# Breeze2_Main_V1.net
KiCad netlist of a schematic drawn in Altium Designer
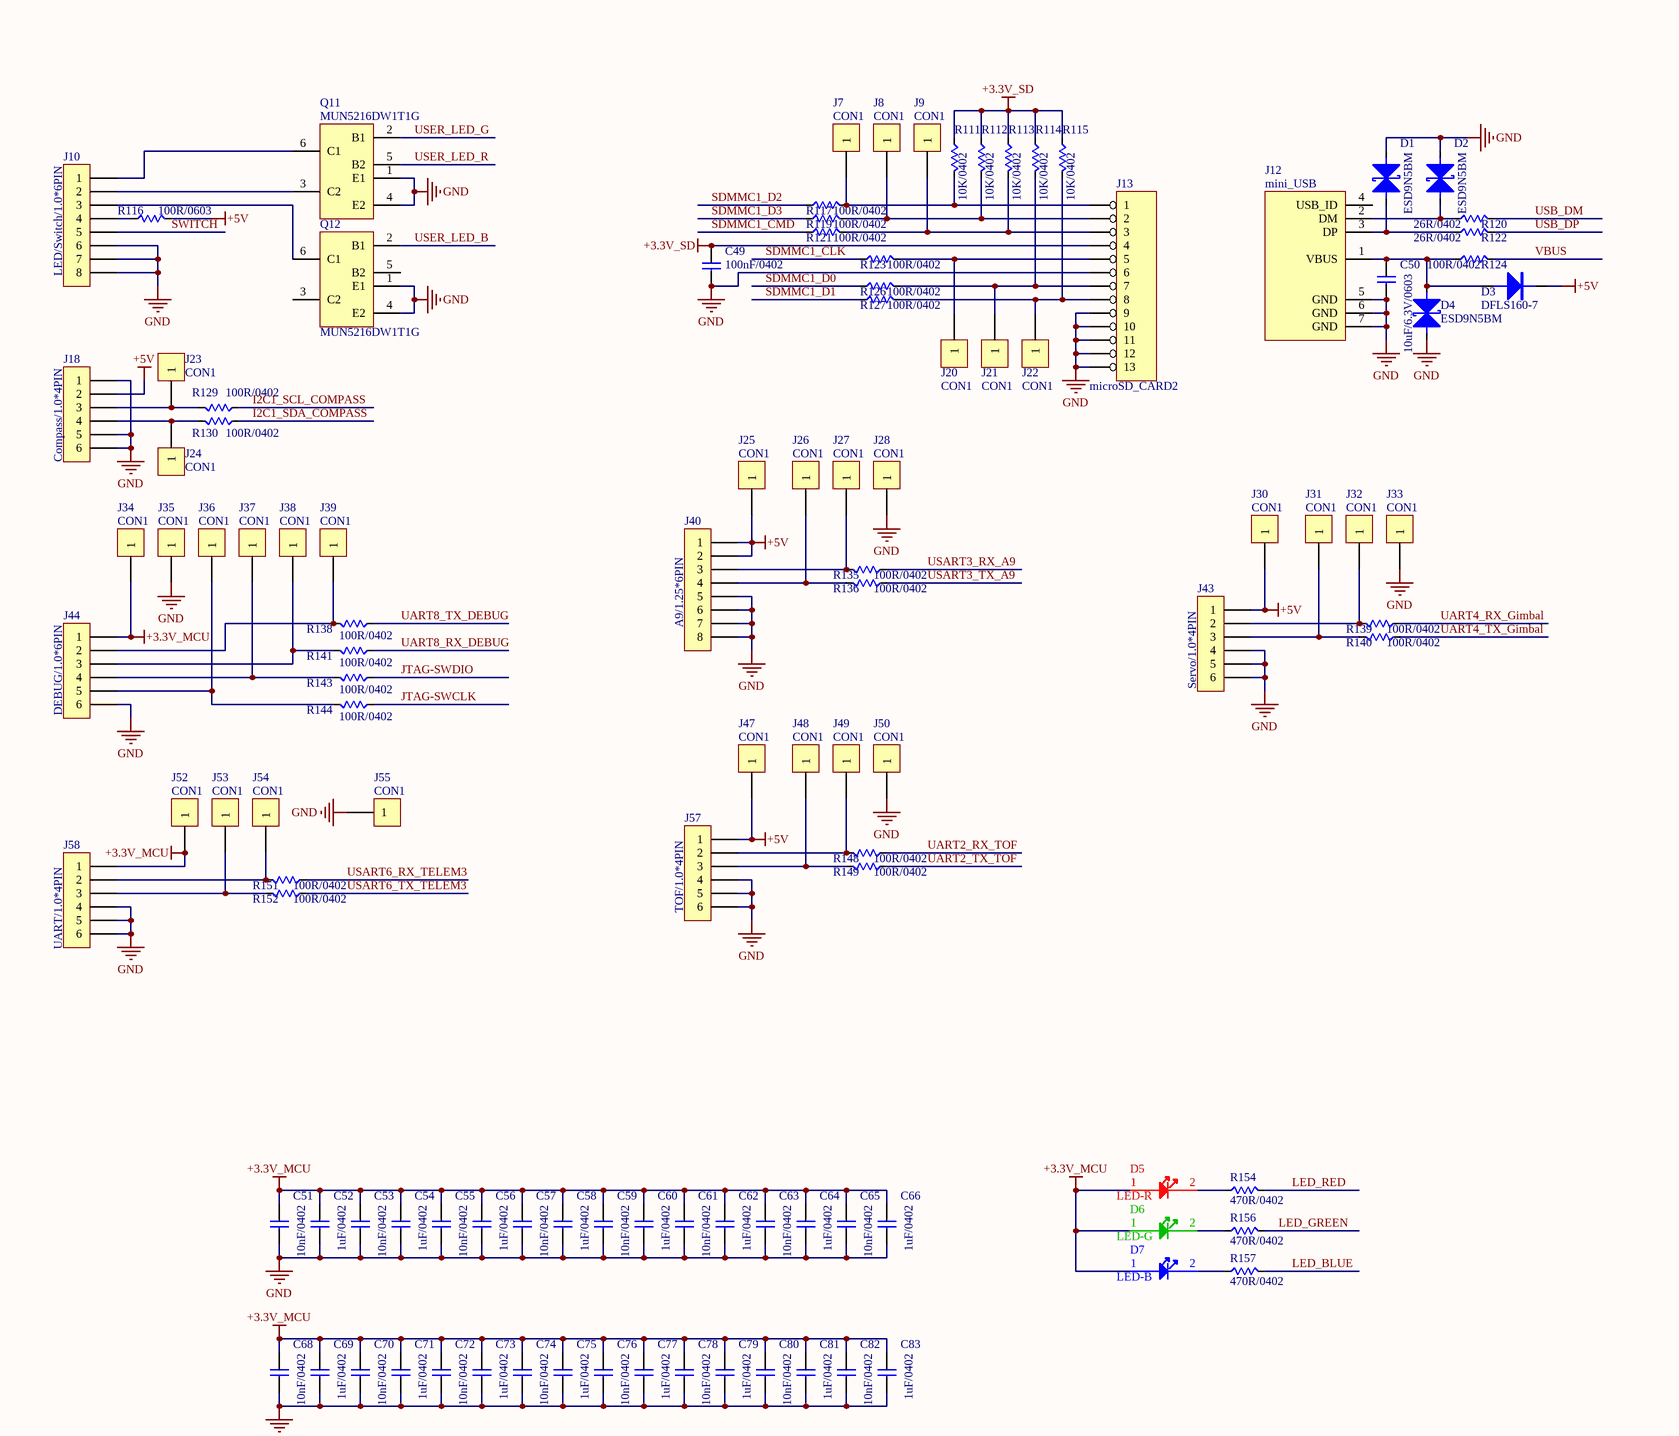
[diagram p0: Breeze2 Main V1.SchDoc, top left]
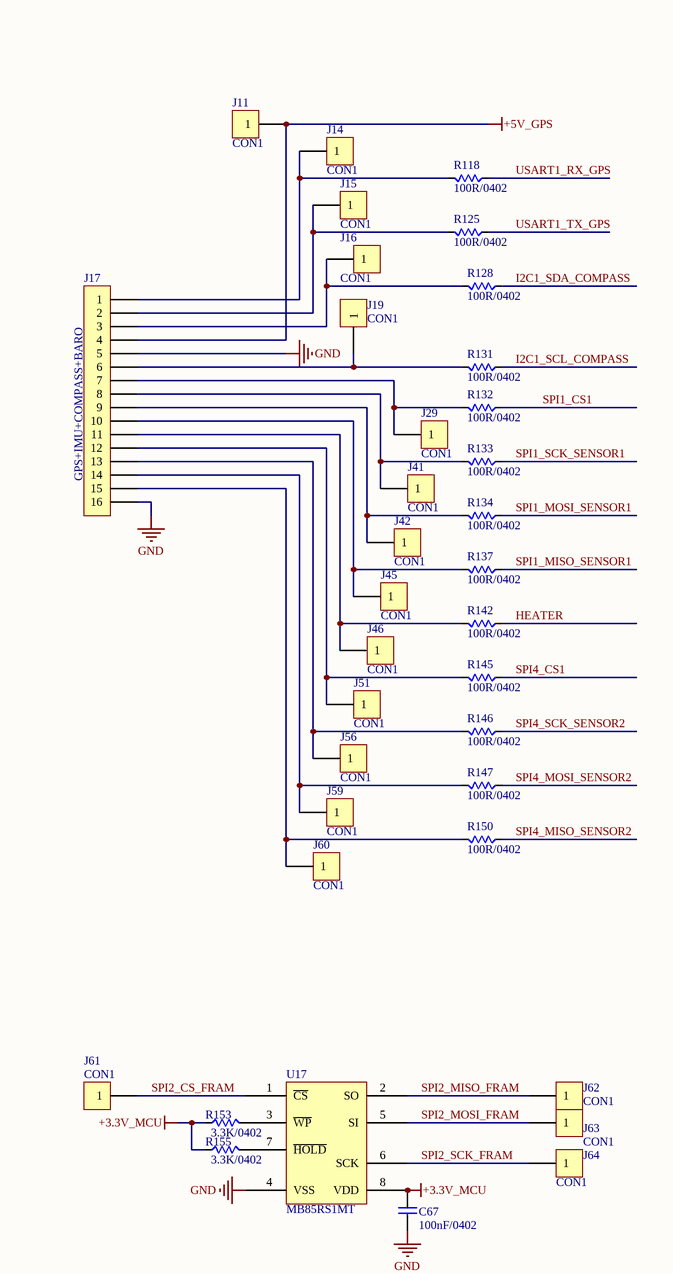
[diagram p1: Breeze2 Main V1.SchDoc, top right]
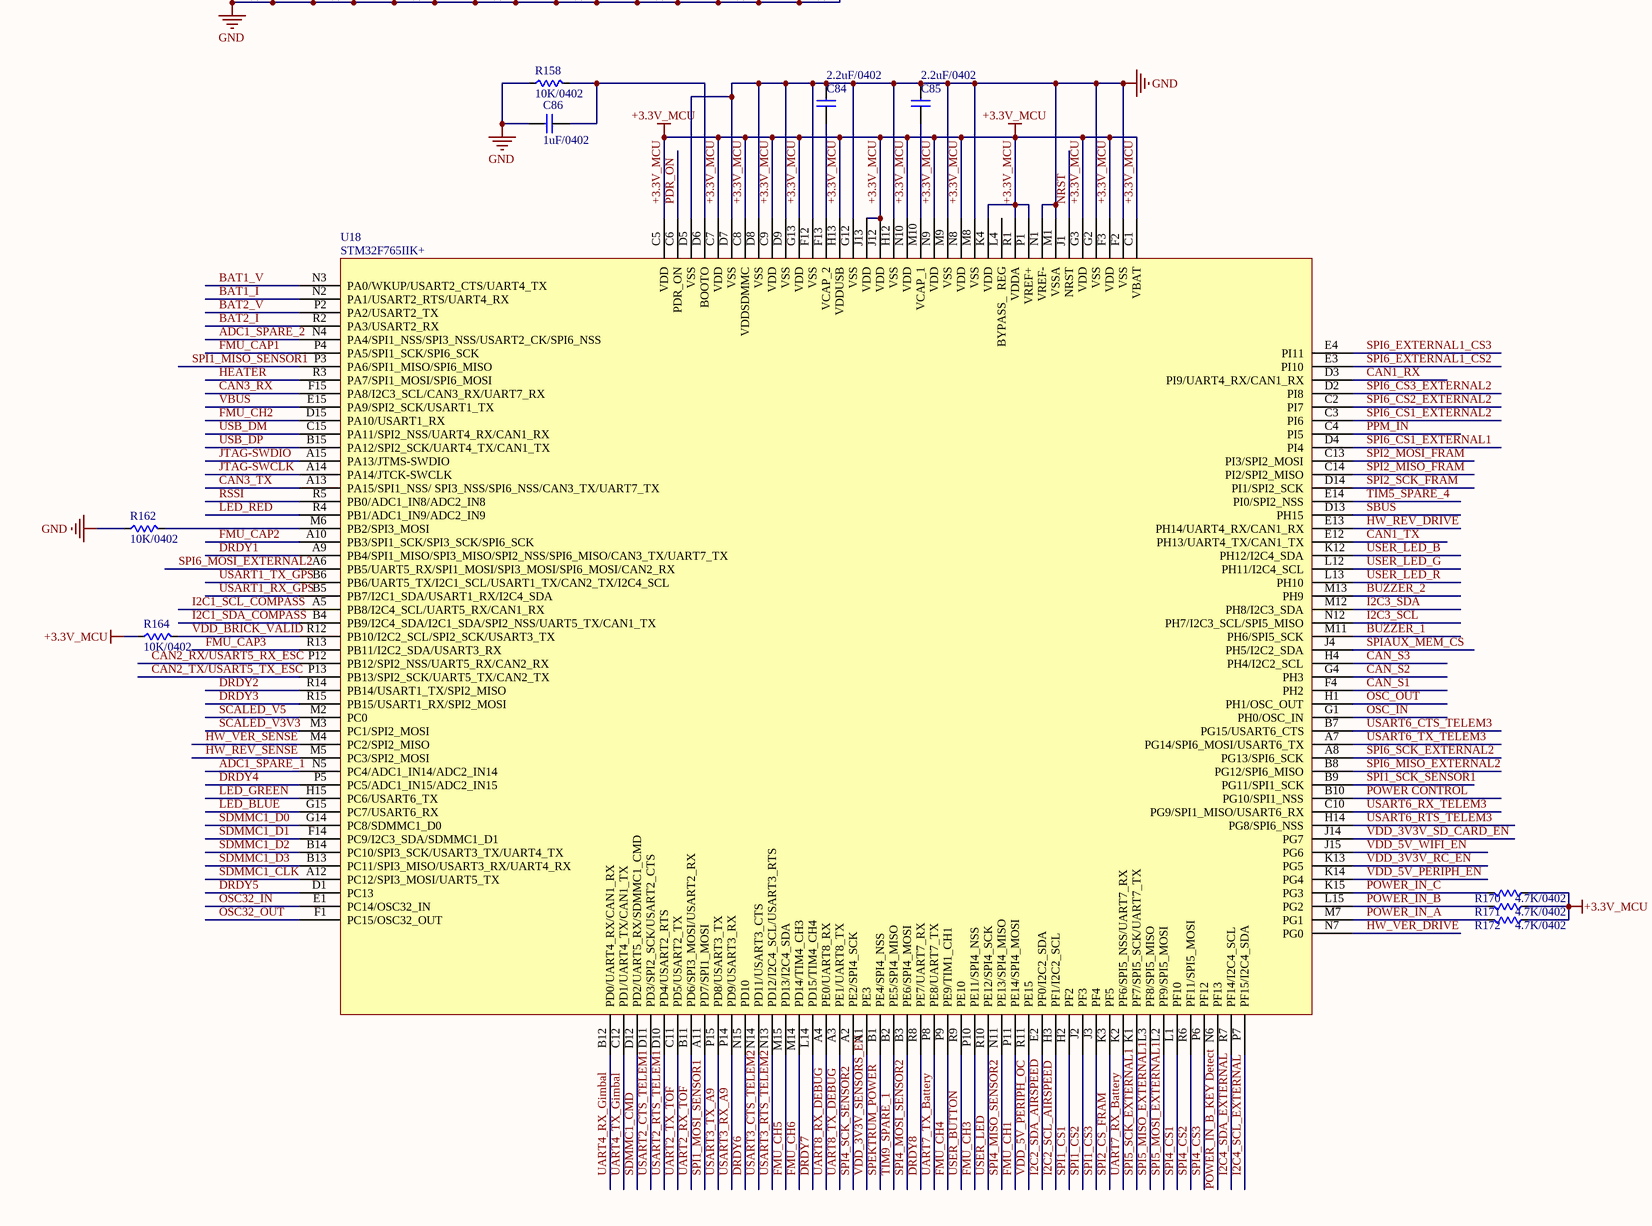
[diagram p2: Breeze2 Main V1.SchDoc, bottom left]
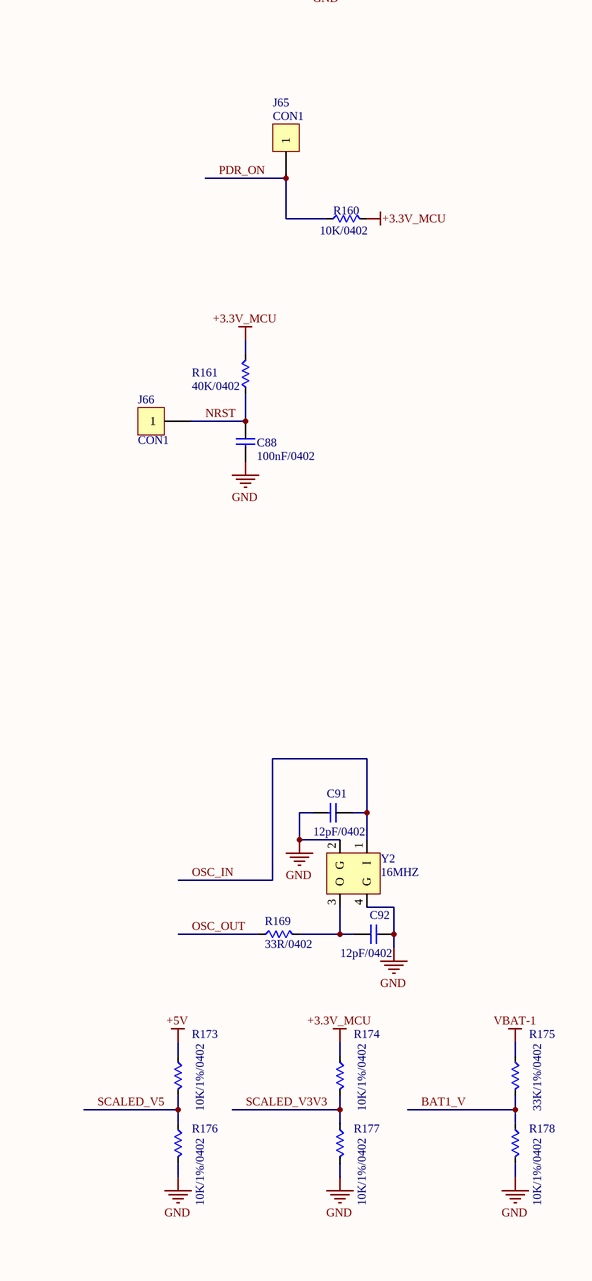
[diagram p3: Breeze2 Main V1.SchDoc, bottom right]

(export (version "E")
  (design (tool "Eeschema 10.0.6"))
  (components
    (comp (ref "C49")
      (value "100nF/0402")
      (footprint "0402C-S")
      (description "CAP")
      (libsource (lib "YUNEEC-SCH") (part "CAP"))
    )
    (comp (ref "C50")
      (value "10uF/6.3V/0603")
      (footprint "0603C-S")
      (description "CAP")
      (libsource (lib "YUNEEC-SCH") (part "CAP"))
    )
    (comp (ref "C51")
      (value "10nF/0402")
      (footprint "0402C-S")
      (description "CAP")
      (libsource (lib "YUNEEC-SCH") (part "CAP"))
    )
    (comp (ref "C52")
      (value "1uF/0402")
      (footprint "0402C-S")
      (description "CAP")
      (libsource (lib "YUNEEC-SCH") (part "CAP"))
    )
    (comp (ref "C53")
      (value "10nF/0402")
      (footprint "0402C-S")
      (description "CAP")
      (libsource (lib "YUNEEC-SCH") (part "CAP"))
    )
    (comp (ref "C54")
      (value "1uF/0402")
      (footprint "0402C-S")
      (description "CAP")
      (libsource (lib "YUNEEC-SCH") (part "CAP"))
    )
    (comp (ref "C55")
      (value "10nF/0402")
      (footprint "0402C-S")
      (description "CAP")
      (libsource (lib "YUNEEC-SCH") (part "CAP"))
    )
    (comp (ref "C56")
      (value "1uF/0402")
      (footprint "0402C-S")
      (description "CAP")
      (libsource (lib "YUNEEC-SCH") (part "CAP"))
    )
    (comp (ref "C57")
      (value "10nF/0402")
      (footprint "0402C-S")
      (description "CAP")
      (libsource (lib "YUNEEC-SCH") (part "CAP"))
    )
    (comp (ref "C58")
      (value "1uF/0402")
      (footprint "0402C-S")
      (description "CAP")
      (libsource (lib "YUNEEC-SCH") (part "CAP"))
    )
    (comp (ref "C59")
      (value "10nF/0402")
      (footprint "0402C-S")
      (description "CAP")
      (libsource (lib "YUNEEC-SCH") (part "CAP"))
    )
    (comp (ref "C60")
      (value "1uF/0402")
      (footprint "0402C-S")
      (description "CAP")
      (libsource (lib "YUNEEC-SCH") (part "CAP"))
    )
    (comp (ref "C61")
      (value "10nF/0402")
      (footprint "0402C-S")
      (description "CAP")
      (libsource (lib "YUNEEC-SCH") (part "CAP"))
    )
    (comp (ref "C62")
      (value "1uF/0402")
      (footprint "0402C-S")
      (description "CAP")
      (libsource (lib "YUNEEC-SCH") (part "CAP"))
    )
    (comp (ref "C63")
      (value "10nF/0402")
      (footprint "0402C-S")
      (description "CAP")
      (libsource (lib "YUNEEC-SCH") (part "CAP"))
    )
    (comp (ref "C64")
      (value "1uF/0402")
      (footprint "0402C-S")
      (description "CAP")
      (libsource (lib "YUNEEC-SCH") (part "CAP"))
    )
    (comp (ref "C65")
      (value "10nF/0402")
      (footprint "0402C-S")
      (description "CAP")
      (libsource (lib "YUNEEC-SCH") (part "CAP"))
    )
    (comp (ref "C66")
      (value "1uF/0402")
      (footprint "0402C-S")
      (description "CAP")
      (libsource (lib "YUNEEC-SCH") (part "CAP"))
    )
    (comp (ref "C67")
      (value "100nF/0402")
      (footprint "0402C-S")
      (description "CAP")
      (libsource (lib "YUNEEC-SCH") (part "CAP"))
    )
    (comp (ref "C68")
      (value "10nF/0402")
      (footprint "0402C-S")
      (description "CAP")
      (libsource (lib "YUNEEC-SCH") (part "CAP"))
    )
    (comp (ref "C69")
      (value "1uF/0402")
      (footprint "0402C-S")
      (description "CAP")
      (libsource (lib "YUNEEC-SCH") (part "CAP"))
    )
    (comp (ref "C70")
      (value "10nF/0402")
      (footprint "0402C-S")
      (description "CAP")
      (libsource (lib "YUNEEC-SCH") (part "CAP"))
    )
    (comp (ref "C71")
      (value "1uF/0402")
      (footprint "0402C-S")
      (description "CAP")
      (libsource (lib "YUNEEC-SCH") (part "CAP"))
    )
    (comp (ref "C72")
      (value "10nF/0402")
      (footprint "0402C-S")
      (description "CAP")
      (libsource (lib "YUNEEC-SCH") (part "CAP"))
    )
    (comp (ref "C73")
      (value "1uF/0402")
      (footprint "0402C-S")
      (description "CAP")
      (libsource (lib "YUNEEC-SCH") (part "CAP"))
    )
    (comp (ref "C74")
      (value "10nF/0402")
      (footprint "0402C-S")
      (description "CAP")
      (libsource (lib "YUNEEC-SCH") (part "CAP"))
    )
    (comp (ref "C75")
      (value "1uF/0402")
      (footprint "0402C-S")
      (description "CAP")
      (libsource (lib "YUNEEC-SCH") (part "CAP"))
    )
    (comp (ref "C76")
      (value "10nF/0402")
      (footprint "0402C-S")
      (description "CAP")
      (libsource (lib "YUNEEC-SCH") (part "CAP"))
    )
    (comp (ref "C77")
      (value "1uF/0402")
      (footprint "0402C-S")
      (description "CAP")
      (libsource (lib "YUNEEC-SCH") (part "CAP"))
    )
    (comp (ref "C78")
      (value "10nF/0402")
      (footprint "0402C-S")
      (description "CAP")
      (libsource (lib "YUNEEC-SCH") (part "CAP"))
    )
    (comp (ref "C79")
      (value "1uF/0402")
      (footprint "0402C-S")
      (description "CAP")
      (libsource (lib "YUNEEC-SCH") (part "CAP"))
    )
    (comp (ref "C80")
      (value "10nF/0402")
      (footprint "0402C-S")
      (description "CAP")
      (libsource (lib "YUNEEC-SCH") (part "CAP"))
    )
    (comp (ref "C81")
      (value "1uF/0402")
      (footprint "0402C-S")
      (description "CAP")
      (libsource (lib "YUNEEC-SCH") (part "CAP"))
    )
    (comp (ref "C82")
      (value "10nF/0402")
      (footprint "0402C-S")
      (description "CAP")
      (libsource (lib "YUNEEC-SCH") (part "CAP"))
    )
    (comp (ref "C83")
      (value "1uF/0402")
      (footprint "0402C-S")
      (description "CAP")
      (libsource (lib "YUNEEC-SCH") (part "CAP"))
    )
    (comp (ref "C84")
      (value "2.2uF/0402")
      (footprint "0402C-S")
      (description "CAP")
      (libsource (lib "YUNEEC-SCH") (part "CAP"))
    )
    (comp (ref "C85")
      (value "2.2uF/0402")
      (footprint "0402C-S")
      (description "CAP")
      (libsource (lib "YUNEEC-SCH") (part "CAP"))
    )
    (comp (ref "C86")
      (value "1uF/0402")
      (footprint "0402C-S")
      (description "CAP")
      (libsource (lib "YUNEEC-SCH") (part "CAP"))
    )
    (comp (ref "C88")
      (value "100nF/0402")
      (footprint "0402C-S")
      (description "CAP")
      (libsource (lib "YUNEEC-SCH") (part "CAP"))
    )
    (comp (ref "C91")
      (value "12pF/0402")
      (footprint "0402C-S")
      (description "CAP")
      (libsource (lib "YUNEEC-SCH") (part "CAP"))
    )
    (comp (ref "C92")
      (value "12pF/0402")
      (footprint "0402C-S")
      (description "CAP")
      (libsource (lib "YUNEEC-SCH") (part "CAP"))
    )
    (comp (ref "D1")
      (value "ESD9N5BM")
      (footprint "0402R-S")
      (description "ESD")
      (libsource (lib "YUNEEC-SCH") (part "DIODE SCHOTTKY"))
    )
    (comp (ref "D2")
      (value "ESD9N5BM")
      (footprint "0402R-S")
      (description "ESD")
      (libsource (lib "YUNEEC-SCH") (part "DIODE SCHOTTKY"))
    )
    (comp (ref "D3")
      (value "DFLS160-7")
      (footprint "POWERDI-123")
      (description "Diode")
      (libsource (lib "YUNEEC-SCH") (part "DIODE"))
    )
    (comp (ref "D4")
      (value "ESD9N5BM")
      (footprint "0402R-S")
      (description "ESD")
      (libsource (lib "YUNEEC-SCH") (part "DIODE SCHOTTKY"))
    )
    (comp (ref "D5") (value "LED-R") (footprint "0603-LED-R") (libsource (lib "YUNEEC-SCH") (part "LED-R")))
    (comp (ref "D6") (value "LED-G") (footprint "0603-LED-G") (libsource (lib "YUNEEC-SCH") (part "LED-G")))
    (comp (ref "D7") (value "LED-B") (footprint "0603-LED-B") (libsource (lib "YUNEEC-SCH") (part "LED-B")))
    (comp (ref "J7")
      (value "CON1")
      (footprint "TPJ1.0")
      (description "Connector")
      (libsource (lib "") (part "CON1_1"))
    )
    (comp (ref "J8")
      (value "CON1")
      (footprint "TPJ1.0")
      (description "Connector")
      (libsource (lib "") (part "CON1_1"))
    )
    (comp (ref "J9")
      (value "CON1")
      (footprint "TPJ1.0")
      (description "Connector")
      (libsource (lib "") (part "CON1_1"))
    )
    (comp (ref "J10")
      (value "LED/Switch/1.0*6PIN")
      (footprint "1.0*6PIN/SMD-H")
      (description "Connector")
      (libsource (lib "YUNEEC-SCH") (part "CON8"))
    )
    (comp (ref "J11")
      (value "CON1")
      (footprint "TPJ1.0")
      (description "Connector")
      (libsource (lib "") (part "CON1_2"))
    )
    (comp (ref "J12")
      (value "mini_USB")
      (footprint "USB-MINI-A")
      (libsource (lib "YUNEEC-SCH") (part "mini_USB"))
    )
    (comp (ref "J13")
      (value "microSD_CARD2")
      (footprint "MICROSD_MINI")
      (libsource (lib "YUNEEC SCH") (part "HEADER 13"))
    )
    (comp (ref "J14")
      (value "CON1")
      (footprint "TPJ1.0")
      (description "Connector")
      (libsource (lib "YUNEEC SCH") (part "CON1"))
    )
    (comp (ref "J15")
      (value "CON1")
      (footprint "TPJ1.0")
      (description "Connector")
      (libsource (lib "YUNEEC SCH") (part "CON1"))
    )
    (comp (ref "J16")
      (value "CON1")
      (footprint "TPJ1.0")
      (description "Connector")
      (libsource (lib "YUNEEC SCH") (part "CON1"))
    )
    (comp (ref "J17")
      (value "GPS+IMU+COMPASS+BARO")
      (footprint "AYF531635")
      (description "Connector")
      (libsource (lib "YUNEEC-SCH") (part "CON16"))
    )
    (comp (ref "J18")
      (value "Compass/1.0*4PIN")
      (footprint "1.0*4PIN/SMD-H")
      (description "Connector")
      (libsource (lib "YUNEEC SCH") (part "CON6"))
    )
    (comp (ref "J19")
      (value "CON1")
      (footprint "TPJ1.0")
      (description "Connector")
      (libsource (lib "") (part "CON1_1"))
    )
    (comp (ref "J20")
      (value "CON1")
      (footprint "TPJ1.0")
      (description "Connector")
      (libsource (lib "*") (part "CON1"))
    )
    (comp (ref "J21")
      (value "CON1")
      (footprint "TPJ1.0")
      (description "Connector")
      (libsource (lib "*") (part "CON1"))
    )
    (comp (ref "J22")
      (value "CON1")
      (footprint "TPJ1.0")
      (description "Connector")
      (libsource (lib "*") (part "CON1"))
    )
    (comp (ref "J23")
      (value "CON1")
      (footprint "TPJ1.0")
      (description "Connector")
      (libsource (lib "YUNEEC SCH") (part "CON1"))
    )
    (comp (ref "J24")
      (value "CON1")
      (footprint "TPJ1.0")
      (description "Connector")
      (libsource (lib "") (part "CON1_2"))
    )
    (comp (ref "J25")
      (value "CON1")
      (footprint "TPJ1.3")
      (description "Connector")
      (libsource (lib "YUNEEC SCH") (part "CON1"))
    )
    (comp (ref "J26")
      (value "CON1")
      (footprint "TPJ1.0")
      (description "Connector")
      (libsource (lib "YUNEEC SCH") (part "CON1"))
    )
    (comp (ref "J27")
      (value "CON1")
      (footprint "TPJ1.0")
      (description "Connector")
      (libsource (lib "YUNEEC SCH") (part "CON1"))
    )
    (comp (ref "J28")
      (value "CON1")
      (footprint "TPJ1.3")
      (description "Connector")
      (libsource (lib "YUNEEC SCH") (part "CON1"))
    )
    (comp (ref "J29")
      (value "CON1")
      (footprint "TPJ1.0")
      (description "Connector")
      (libsource (lib "YUNEEC SCH") (part "CON1"))
    )
    (comp (ref "J30")
      (value "CON1")
      (footprint "TPJ1.3")
      (description "Connector")
      (libsource (lib "YUNEEC SCH") (part "CON1"))
    )
    (comp (ref "J31")
      (value "CON1")
      (footprint "TPJ1.0")
      (description "Connector")
      (libsource (lib "YUNEEC SCH") (part "CON1"))
    )
    (comp (ref "J32")
      (value "CON1")
      (footprint "TPJ1.0")
      (description "Connector")
      (libsource (lib "YUNEEC SCH") (part "CON1"))
    )
    (comp (ref "J33")
      (value "CON1")
      (footprint "TPJ1.3")
      (description "Connector")
      (libsource (lib "YUNEEC SCH") (part "CON1"))
    )
    (comp (ref "J34")
      (value "CON1")
      (footprint "TPJ1.0")
      (description "Connector")
      (libsource (lib "YUNEEC SCH") (part "CON1"))
    )
    (comp (ref "J35")
      (value "CON1")
      (footprint "TPJ1.0")
      (description "Connector")
      (libsource (lib "YUNEEC SCH") (part "CON1"))
    )
    (comp (ref "J36")
      (value "CON1")
      (footprint "TPJ1.0")
      (description "Connector")
      (libsource (lib "YUNEEC SCH") (part "CON1"))
    )
    (comp (ref "J37")
      (value "CON1")
      (footprint "TPJ1.0")
      (description "Connector")
      (libsource (lib "YUNEEC SCH") (part "CON1"))
    )
    (comp (ref "J38")
      (value "CON1")
      (footprint "TPJ1.0")
      (description "Connector")
      (libsource (lib "YUNEEC SCH") (part "CON1"))
    )
    (comp (ref "J39")
      (value "CON1")
      (footprint "TPJ1.0")
      (description "Connector")
      (libsource (lib "YUNEEC SCH") (part "CON1"))
    )
    (comp (ref "J40")
      (value "A9/1.25*6PIN")
      (footprint "1.25*6PIN/SMD")
      (description "Connector")
      (libsource (lib "YUNEEC-SCH") (part "CON8"))
    )
    (comp (ref "J41")
      (value "CON1")
      (footprint "TPJ1.0")
      (description "Connector")
      (libsource (lib "YUNEEC SCH") (part "CON1"))
    )
    (comp (ref "J42")
      (value "CON1")
      (footprint "TPJ1.0")
      (description "Connector")
      (libsource (lib "YUNEEC SCH") (part "CON1"))
    )
    (comp (ref "J43")
      (value "Servo/1.0*4PIN")
      (footprint "1.0*4PIN/SMD")
      (description "Connector")
      (libsource (lib "YUNEEC SCH") (part "CON6"))
    )
    (comp (ref "J44")
      (value "DEBUG/1.0*6PIN")
      (footprint "1.0*6PIN/SMD")
      (description "Connector")
      (libsource (lib "YUNEEC SCH") (part "CON6"))
    )
    (comp (ref "J45")
      (value "CON1")
      (footprint "TPJ1.0")
      (description "Connector")
      (libsource (lib "YUNEEC SCH") (part "CON1"))
    )
    (comp (ref "J46")
      (value "CON1")
      (footprint "TPJ1.0")
      (description "Connector")
      (libsource (lib "YUNEEC SCH") (part "CON1"))
    )
    (comp (ref "J47")
      (value "CON1")
      (footprint "TPJ1.2")
      (description "Connector")
      (libsource (lib "YUNEEC SCH") (part "CON1"))
    )
    (comp (ref "J48")
      (value "CON1")
      (footprint "TPJ1.0")
      (description "Connector")
      (libsource (lib "YUNEEC SCH") (part "CON1"))
    )
    (comp (ref "J49")
      (value "CON1")
      (footprint "TPJ1.0")
      (description "Connector")
      (libsource (lib "YUNEEC SCH") (part "CON1"))
    )
    (comp (ref "J50")
      (value "CON1")
      (footprint "TPJ1.2")
      (description "Connector")
      (libsource (lib "YUNEEC SCH") (part "CON1"))
    )
    (comp (ref "J51")
      (value "CON1")
      (footprint "TPJ1.0")
      (description "Connector")
      (libsource (lib "YUNEEC SCH") (part "CON1"))
    )
    (comp (ref "J52")
      (value "CON1")
      (footprint "TPJ1.0")
      (description "Connector")
      (libsource (lib "YUNEEC SCH") (part "CON1"))
    )
    (comp (ref "J53")
      (value "CON1")
      (footprint "TPJ1.0")
      (description "Connector")
      (libsource (lib "YUNEEC SCH") (part "CON1"))
    )
    (comp (ref "J54")
      (value "CON1")
      (footprint "TPJ1.0")
      (description "Connector")
      (libsource (lib "YUNEEC SCH") (part "CON1"))
    )
    (comp (ref "J55")
      (value "CON1")
      (footprint "TPJ1.0")
      (description "Connector")
      (libsource (lib "") (part "CON1_1"))
    )
    (comp (ref "J56")
      (value "CON1")
      (footprint "TPJ1.0")
      (description "Connector")
      (libsource (lib "YUNEEC SCH") (part "CON1"))
    )
    (comp (ref "J57")
      (value "TOF/1.0*4PIN")
      (footprint "1.0*4PIN/SMD-H")
      (description "Connector")
      (libsource (lib "YUNEEC SCH") (part "CON6"))
    )
    (comp (ref "J58")
      (value "UART/1.0*4PIN")
      (footprint "1.0*4PIN/SMD")
      (description "Connector")
      (libsource (lib "YUNEEC SCH") (part "CON6"))
    )
    (comp (ref "J59")
      (value "CON1")
      (footprint "TPJ1.0")
      (description "Connector")
      (libsource (lib "YUNEEC SCH") (part "CON1"))
    )
    (comp (ref "J60")
      (value "CON1")
      (footprint "TPJ1.0")
      (description "Connector")
      (libsource (lib "YUNEEC SCH") (part "CON1"))
    )
    (comp (ref "J61")
      (value "CON1")
      (footprint "TPJ1.0")
      (description "Connector")
      (libsource (lib "") (part "CON1_3"))
    )
    (comp (ref "J62")
      (value "CON1")
      (footprint "TPJ1.0")
      (description "Connector")
      (libsource (lib "") (part "CON1_1"))
    )
    (comp (ref "J63")
      (value "CON1")
      (footprint "TPJ1.0")
      (description "Connector")
      (libsource (lib "") (part "CON1_1"))
    )
    (comp (ref "J64")
      (value "CON1")
      (footprint "TPJ1.0")
      (description "Connector")
      (libsource (lib "") (part "CON1_1"))
    )
    (comp (ref "J65")
      (value "CON1")
      (footprint "TPJ1.0")
      (description "Connector")
      (libsource (lib "YUNEEC SCH") (part "CON1"))
    )
    (comp (ref "J66")
      (value "CON1")
      (footprint "TPJ1.0")
      (description "Connector")
      (libsource (lib "") (part "CON1_3"))
    )
    (comp (ref "Q11")
      (value "MUN5216DW1T1G")
      (footprint "SOT-363A")
      (libsource (lib "YUNEEC-SCH") (part "MUN5216DW1T1"))
    )
    (comp (ref "Q12")
      (value "MUN5216DW1T1G")
      (footprint "SOT-363A")
      (libsource (lib "YUNEEC-SCH") (part "MUN5216DW1T1"))
    )
    (comp (ref "R111") (value "10K/0402") (footprint "0402R-S") (libsource (lib "YUNEEC-SCH") (part "RES")))
    (comp (ref "R112") (value "10K/0402") (footprint "0402R-S") (libsource (lib "YUNEEC-SCH") (part "RES")))
    (comp (ref "R113") (value "10K/0402") (footprint "0402R-S") (libsource (lib "YUNEEC-SCH") (part "RES")))
    (comp (ref "R114") (value "10K/0402") (footprint "0402R-S") (libsource (lib "YUNEEC-SCH") (part "RES")))
    (comp (ref "R115") (value "10K/0402") (footprint "0402R-S") (libsource (lib "YUNEEC-SCH") (part "RES")))
    (comp (ref "R116") (value "100R/0603") (footprint "0603R-S") (libsource (lib "YUNEEC-SCH") (part "RES")))
    (comp (ref "R117") (value "100R/0402") (footprint "0402R-S") (libsource (lib "YUNEEC-SCH") (part "RES")))
    (comp (ref "R118") (value "100R/0402") (footprint "0402R-S") (libsource (lib "YUNEEC-SCH") (part "RES")))
    (comp (ref "R119") (value "100R/0402") (footprint "0402R-S") (libsource (lib "YUNEEC-SCH") (part "RES")))
    (comp (ref "R120") (value "26R/0402") (footprint "0402R-S") (libsource (lib "YUNEEC-SCH") (part "RES")))
    (comp (ref "R121") (value "100R/0402") (footprint "0402R-S") (libsource (lib "YUNEEC-SCH") (part "RES")))
    (comp (ref "R122") (value "26R/0402") (footprint "0402R-S") (libsource (lib "YUNEEC-SCH") (part "RES")))
    (comp (ref "R123") (value "100R/0402") (footprint "0402R-S") (libsource (lib "YUNEEC-SCH") (part "RES")))
    (comp (ref "R124") (value "100R/0402") (footprint "0402R-S") (libsource (lib "YUNEEC-SCH") (part "RES")))
    (comp (ref "R125") (value "100R/0402") (footprint "0402R-S") (libsource (lib "YUNEEC-SCH") (part "RES")))
    (comp (ref "R126") (value "100R/0402") (footprint "0402R-S") (libsource (lib "YUNEEC-SCH") (part "RES")))
    (comp (ref "R127") (value "100R/0402") (footprint "0402R-S") (libsource (lib "YUNEEC-SCH") (part "RES")))
    (comp (ref "R128") (value "100R/0402") (footprint "0402R-S") (libsource (lib "YUNEEC-SCH") (part "RES")))
    (comp (ref "R129") (value "100R/0402") (footprint "0402R-S") (libsource (lib "YUNEEC-SCH") (part "RES")))
    (comp (ref "R130") (value "100R/0402") (footprint "0402R-S") (libsource (lib "YUNEEC-SCH") (part "RES")))
    (comp (ref "R131") (value "100R/0402") (footprint "0402R-S") (libsource (lib "YUNEEC-SCH") (part "RES")))
    (comp (ref "R132") (value "100R/0402") (footprint "0402R-S") (libsource (lib "YUNEEC-SCH") (part "RES")))
    (comp (ref "R133") (value "100R/0402") (footprint "0402R-S") (libsource (lib "YUNEEC-SCH") (part "RES")))
    (comp (ref "R134") (value "100R/0402") (footprint "0402R-S") (libsource (lib "YUNEEC-SCH") (part "RES")))
    (comp (ref "R135") (value "100R/0402") (footprint "0402R-S") (libsource (lib "YUNEEC-SCH") (part "RES")))
    (comp (ref "R136") (value "100R/0402") (footprint "0402R-S") (libsource (lib "YUNEEC-SCH") (part "RES")))
    (comp (ref "R137") (value "100R/0402") (footprint "0402R-S") (libsource (lib "YUNEEC-SCH") (part "RES")))
    (comp (ref "R138") (value "100R/0402") (footprint "0402R-S") (libsource (lib "YUNEEC-SCH") (part "RES")))
    (comp (ref "R139") (value "100R/0402") (footprint "0402R-S") (libsource (lib "YUNEEC-SCH") (part "RES")))
    (comp (ref "R140") (value "100R/0402") (footprint "0402R-S") (libsource (lib "YUNEEC-SCH") (part "RES")))
    (comp (ref "R141") (value "100R/0402") (footprint "0402R-S") (libsource (lib "YUNEEC-SCH") (part "RES")))
    (comp (ref "R142") (value "100R/0402") (footprint "0402R-S") (libsource (lib "YUNEEC-SCH") (part "RES")))
    (comp (ref "R143") (value "100R/0402") (footprint "0402R-S") (libsource (lib "YUNEEC-SCH") (part "RES")))
    (comp (ref "R144") (value "100R/0402") (footprint "0402R-S") (libsource (lib "YUNEEC-SCH") (part "RES")))
    (comp (ref "R145") (value "100R/0402") (footprint "0402R-S") (libsource (lib "YUNEEC-SCH") (part "RES")))
    (comp (ref "R146") (value "100R/0402") (footprint "0402R-S") (libsource (lib "YUNEEC-SCH") (part "RES")))
    (comp (ref "R147") (value "100R/0402") (footprint "0402R-S") (libsource (lib "YUNEEC-SCH") (part "RES")))
    (comp (ref "R148") (value "100R/0402") (footprint "0402R-S") (libsource (lib "YUNEEC-SCH") (part "RES")))
    (comp (ref "R149") (value "100R/0402") (footprint "0402R-S") (libsource (lib "YUNEEC-SCH") (part "RES")))
    (comp (ref "R150") (value "100R/0402") (footprint "0402R-S") (libsource (lib "YUNEEC-SCH") (part "RES")))
    (comp (ref "R151") (value "100R/0402") (footprint "0402R-S") (libsource (lib "YUNEEC-SCH") (part "RES")))
    (comp (ref "R152") (value "100R/0402") (footprint "0402R-S") (libsource (lib "YUNEEC-SCH") (part "RES")))
    (comp (ref "R153") (value "3.3K/0402") (footprint "0402R-S") (libsource (lib "YUNEEC-SCH") (part "RES")))
    (comp (ref "R154") (value "470R/0402") (footprint "0402R-S") (libsource (lib "YUNEEC-SCH") (part "RES")))
    (comp (ref "R155") (value "3.3K/0402") (footprint "0402R-S") (libsource (lib "YUNEEC-SCH") (part "RES")))
    (comp (ref "R156") (value "470R/0402") (footprint "0402R-S") (libsource (lib "YUNEEC-SCH") (part "RES")))
    (comp (ref "R157") (value "470R/0402") (footprint "0402R-S") (libsource (lib "YUNEEC-SCH") (part "RES")))
    (comp (ref "R158") (value "10K/0402") (footprint "0402R-S") (libsource (lib "YUNEEC-SCH") (part "RES")))
    (comp (ref "R160") (value "10K/0402") (footprint "0402R-S") (libsource (lib "YUNEEC-SCH") (part "RES")))
    (comp (ref "R161") (value "40K/0402") (footprint "0402R-S") (libsource (lib "YUNEEC-SCH") (part "RES")))
    (comp (ref "R162") (value "10K/0402") (footprint "0402R-S") (libsource (lib "YUNEEC-SCH") (part "RES")))
    (comp (ref "R164") (value "10K/0402") (footprint "0402R-S") (libsource (lib "YUNEEC-SCH") (part "RES")))
    (comp (ref "R169") (value "33R/0402") (footprint "0402R-S") (libsource (lib "YUNEEC-SCH") (part "RES")))
    (comp (ref "R170") (value "4.7K/0402") (footprint "0402R-S") (libsource (lib "YUNEEC-SCH") (part "RES")))
    (comp (ref "R171") (value "4.7K/0402") (footprint "0402R-S") (libsource (lib "YUNEEC-SCH") (part "RES")))
    (comp (ref "R172") (value "4.7K/0402") (footprint "0402R-S") (libsource (lib "YUNEEC-SCH") (part "RES")))
    (comp (ref "R173")
      (value "10K/1%/0402")
      (footprint "0402R-S")
      (libsource (lib "YUNEEC-SCH") (part "RES"))
    )
    (comp (ref "R174")
      (value "10K/1%/0402")
      (footprint "0402R-S")
      (libsource (lib "YUNEEC-SCH") (part "RES"))
    )
    (comp (ref "R175")
      (value "33K/1%/0402")
      (footprint "0402R-S")
      (libsource (lib "YUNEEC-SCH") (part "RES"))
    )
    (comp (ref "R176")
      (value "10K/1%/0402")
      (footprint "0402R-S")
      (libsource (lib "YUNEEC-SCH") (part "RES"))
    )
    (comp (ref "R177")
      (value "10K/1%/0402")
      (footprint "0402R-S")
      (libsource (lib "YUNEEC-SCH") (part "RES"))
    )
    (comp (ref "R178")
      (value "10K/1%/0402")
      (footprint "0402R-S")
      (libsource (lib "YUNEEC-SCH") (part "RES"))
    )
    (comp (ref "U17")
      (value "MB85RS1MT")
      (footprint "SO-8A")
      (libsource (lib "YUNEEC SCH") (part "MB85RS1MT"))
    )
    (comp (ref "U18")
      (value "STM32F765IIK+")
      (footprint "UFBGA176/10*10")
      (libsource (lib "YUNEEC SCH") (part "STM32F765IIK+"))
    )
    (comp (ref "Y2") (value "16MHZ") (footprint "Y3225") (libsource (lib "YUNEEC SCH") (part "Crystal2")))
  )
  (nets
    (net (code "1") (name "+3.3V_MCU") (class "Default")
      (node (ref "C51") (pin "1") (pinfunction "1_1") (pintype "passive"))
      (node (ref "C52") (pin "1") (pinfunction "1_1") (pintype "passive"))
      (node (ref "C53") (pin "1") (pinfunction "1_1") (pintype "passive"))
      (node (ref "C54") (pin "1") (pinfunction "1_1") (pintype "passive"))
      (node (ref "C55") (pin "1") (pinfunction "1_1") (pintype "passive"))
      (node (ref "C56") (pin "1") (pinfunction "1_1") (pintype "passive"))
      (node (ref "C57") (pin "1") (pinfunction "1_1") (pintype "passive"))
      (node (ref "C58") (pin "1") (pinfunction "1_1") (pintype "passive"))
      (node (ref "C59") (pin "1") (pinfunction "1_1") (pintype "passive"))
      (node (ref "C60") (pin "1") (pinfunction "1_1") (pintype "passive"))
      (node (ref "C61") (pin "1") (pinfunction "1_1") (pintype "passive"))
      (node (ref "C62") (pin "1") (pinfunction "1_1") (pintype "passive"))
      (node (ref "C63") (pin "1") (pinfunction "1_1") (pintype "passive"))
      (node (ref "C64") (pin "1") (pinfunction "1_1") (pintype "passive"))
      (node (ref "C65") (pin "1") (pinfunction "1_1") (pintype "passive"))
      (node (ref "C66") (pin "1") (pinfunction "1_1") (pintype "passive"))
      (node (ref "C67") (pin "1") (pinfunction "1_1") (pintype "passive"))
      (node (ref "C68") (pin "1") (pinfunction "1_1") (pintype "passive"))
      (node (ref "C69") (pin "1") (pinfunction "1_1") (pintype "passive"))
      (node (ref "C70") (pin "1") (pinfunction "1_1") (pintype "passive"))
      (node (ref "C71") (pin "1") (pinfunction "1_1") (pintype "passive"))
      (node (ref "C72") (pin "1") (pinfunction "1_1") (pintype "passive"))
      (node (ref "C73") (pin "1") (pinfunction "1_1") (pintype "passive"))
      (node (ref "C74") (pin "1") (pinfunction "1_1") (pintype "passive"))
      (node (ref "C75") (pin "1") (pinfunction "1_1") (pintype "passive"))
      (node (ref "C76") (pin "1") (pinfunction "1_1") (pintype "passive"))
      (node (ref "C77") (pin "1") (pinfunction "1_1") (pintype "passive"))
      (node (ref "C78") (pin "1") (pinfunction "1_1") (pintype "passive"))
      (node (ref "C79") (pin "1") (pinfunction "1_1") (pintype "passive"))
      (node (ref "C80") (pin "1") (pinfunction "1_1") (pintype "passive"))
      (node (ref "C81") (pin "1") (pinfunction "1_1") (pintype "passive"))
      (node (ref "C82") (pin "1") (pinfunction "1_1") (pintype "passive"))
      (node (ref "C83") (pin "1") (pinfunction "1_1") (pintype "passive"))
      (node (ref "D5") (pin "1") (pinfunction "A_1") (pintype "passive"))
      (node (ref "D6") (pin "1") (pinfunction "A_1") (pintype "passive"))
      (node (ref "D7") (pin "1") (pinfunction "A_1") (pintype "passive"))
      (node (ref "J34") (pin "1") (pinfunction "1_1") (pintype "passive"))
      (node (ref "J44") (pin "1") (pinfunction "1_1") (pintype "passive"))
      (node (ref "J52") (pin "1") (pinfunction "1_1") (pintype "passive"))
      (node (ref "J58") (pin "1") (pinfunction "1_1") (pintype "passive"))
      (node (ref "R153") (pin "1") (pinfunction "1_1") (pintype "passive"))
      (node (ref "R155") (pin "1") (pinfunction "1_1") (pintype "passive"))
      (node (ref "R160") (pin "2") (pinfunction "2_2") (pintype "passive"))
      (node (ref "R161") (pin "2") (pinfunction "2_2") (pintype "passive"))
      (node (ref "R164") (pin "1") (pinfunction "1_1") (pintype "passive"))
      (node (ref "R170") (pin "1") (pinfunction "1_1") (pintype "passive"))
      (node (ref "R171") (pin "1") (pinfunction "1_1") (pintype "passive"))
      (node (ref "R172") (pin "1") (pinfunction "1_1") (pintype "passive"))
      (node (ref "R174") (pin "1") (pinfunction "1_1") (pintype "passive"))
      (node (ref "U17") (pin "8") (pinfunction "VDD_8") (pintype "passive"))
      (node (ref "U18") (pin "C1") (pinfunction "VBAT_C1") (pintype "passive"))
      (node (ref "U18") (pin "C5") (pinfunction "VDD_C5") (pintype "passive"))
      (node (ref "U18") (pin "C7") (pinfunction "VDD_C7") (pintype "passive"))
      (node (ref "U18") (pin "C8") (pinfunction "VDDSDMMC_C8") (pintype "passive"))
      (node (ref "U18") (pin "C9") (pinfunction "VDD_C9") (pintype "passive"))
      (node (ref "U18") (pin "F3") (pinfunction "VDD_F3") (pintype "passive"))
      (node (ref "U18") (pin "G13") (pinfunction "VDD_G13") (pintype "passive"))
      (node (ref "U18") (pin "G3") (pinfunction "VDD_G3") (pintype "passive"))
      (node (ref "U18") (pin "H13") (pinfunction "VDDUSB_H13") (pintype "passive"))
      (node (ref "U18") (pin "J12") (pinfunction "VDD_J12") (pintype "passive"))
      (node (ref "U18") (pin "J13") (pinfunction "VDD_J13") (pintype "passive"))
      (node (ref "U18") (pin "K4") (pinfunction "VDD_K4") (pintype "passive"))
      (node (ref "U18") (pin "N10") (pinfunction "VDD_N10") (pintype "passive"))
      (node (ref "U18") (pin "N8") (pinfunction "VDD_N8") (pintype "passive"))
      (node (ref "U18") (pin "N9") (pinfunction "VDD_N9") (pintype "passive"))
      (node (ref "U18") (pin "P1") (pinfunction "VREF+_P1") (pintype "passive"))
      (node (ref "U18") (pin "R1") (pinfunction "VDDA_R1") (pintype "passive"))
    )
    (net (code "2") (name "+3.3V_SD") (class "Default")
      (node (ref "C49") (pin "1") (pinfunction "1_1") (pintype "passive"))
      (node (ref "J13") (pin "4") (pinfunction "4_4") (pintype "passive"))
      (node (ref "R111") (pin "1") (pinfunction "1_1") (pintype "passive"))
      (node (ref "R112") (pin "1") (pinfunction "1_1") (pintype "passive"))
      (node (ref "R113") (pin "1") (pinfunction "1_1") (pintype "passive"))
      (node (ref "R114") (pin "1") (pinfunction "1_1") (pintype "passive"))
      (node (ref "R115") (pin "1") (pinfunction "1_1") (pintype "passive"))
    )
    (net (code "3") (name "+5V") (class "Default")
      (node (ref "D3") (pin "2") (pinfunction "K_2") (pintype "passive"))
      (node (ref "J18") (pin "2") (pinfunction "2_2") (pintype "passive"))
      (node (ref "J25") (pin "1") (pinfunction "1_1") (pintype "passive"))
      (node (ref "J30") (pin "1") (pinfunction "1_1") (pintype "passive"))
      (node (ref "J40") (pin "1") (pinfunction "1_1") (pintype "passive"))
      (node (ref "J40") (pin "2") (pinfunction "2_2") (pintype "passive"))
      (node (ref "J43") (pin "1") (pinfunction "1_1") (pintype "passive"))
      (node (ref "J47") (pin "1") (pinfunction "1_1") (pintype "passive"))
      (node (ref "J57") (pin "1") (pinfunction "1_1") (pintype "passive"))
      (node (ref "R116") (pin "2") (pinfunction "2_2") (pintype "passive"))
      (node (ref "R173") (pin "1") (pinfunction "1_1") (pintype "passive"))
    )
    (net (code "4") (name "+5V_GPS") (class "Default")
      (node (ref "J11") (pin "1") (pinfunction "1_1") (pintype "passive"))
      (node (ref "J17") (pin "4") (pinfunction "4_4") (pintype "passive"))
    )
    (net (code "5") (name "/ADC1_SPARE_1") (class "Default")
      (node (ref "U18") (pin "N5") (pinfunction "PC4/ADC1_IN14/ADC2_IN14_N5") (pintype "passive"))
    )
    (net (code "6") (name "/ADC1_SPARE_2") (class "Default")
      (node (ref "U18") (pin "N4") (pinfunction "PA4/SPI1_NSS/SPI3_NSS/USART2_CK/SPI6_NSS_N4") (pintype "passive"))
    )
    (net (code "7") (name "/BAT1_I") (class "Default")
      (node (ref "U18") (pin "N2") (pinfunction "PA1/USART2_RTS/UART4_RX_N2") (pintype "passive"))
    )
    (net (code "8") (name "/BAT1_V") (class "Default")
      (node (ref "R175") (pin "2") (pinfunction "2_2") (pintype "passive"))
      (node (ref "R178") (pin "1") (pinfunction "1_1") (pintype "passive"))
      (node (ref "U18") (pin "N3") (pinfunction "PA0/WKUP/USART2_CTS/UART4_TX_N3") (pintype "passive"))
    )
    (net (code "9") (name "/BAT2_I") (class "Default")
      (node (ref "U18") (pin "R2") (pinfunction "PA3/USART2_RX_R2") (pintype "passive"))
    )
    (net (code "10") (name "/BAT2_V") (class "Default")
      (node (ref "U18") (pin "P2") (pinfunction "PA2/USART2_TX_P2") (pintype "passive"))
    )
    (net (code "11") (name "/BUZZER_1") (class "Default")
      (node (ref "U18") (pin "M11") (pinfunction "PH6/SPI5_SCK_M11") (pintype "passive"))
    )
    (net (code "12") (name "/BUZZER_2") (class "Default")
      (node (ref "U18") (pin "M13") (pinfunction "PH9_M13") (pintype "passive"))
    )
    (net (code "13") (name "/CAN1_RX") (class "Default")
      (node (ref "U18") (pin "D3") (pinfunction "PI9/UART4_RX/CAN1_RX_D3") (pintype "passive"))
    )
    (net (code "14") (name "/CAN1_TX") (class "Default")
      (node (ref "U18") (pin "E12") (pinfunction "PH13/UART4_TX/CAN1_TX_E12") (pintype "passive"))
    )
    (net (code "15") (name "/CAN2_RX{slash}USART5_RX_ESC") (class "Default")
      (node (ref "U18") (pin "P12") (pinfunction "PB12/SPI2_NSS/UART5_RX/CAN2_RX_P12") (pintype "passive"))
    )
    (net (code "16") (name "/CAN2_TX{slash}USART5_TX_ESC") (class "Default")
      (node (ref "U18") (pin "P13") (pinfunction "PB13/SPI2_SCK/UART5_TX/CAN2_TX_P13") (pintype "passive"))
    )
    (net (code "17") (name "/CAN3_RX") (class "Default")
      (node (ref "U18") (pin "F15") (pinfunction "PA8/I2C3_SCL/CAN3_RX/UART7_RX_F15") (pintype "passive"))
    )
    (net (code "18") (name "/CAN3_TX") (class "Default")
      (node (ref "U18") (pin "A13") (pinfunction "PA15/SPI1_NSS/_SPI3_NSS/SPI6_NSS/CAN3_TX/UART7_TX_A13") (pintype "passive"))
    )
    (net (code "19") (name "/CAN_S1") (class "Default")
      (node (ref "U18") (pin "F4") (pinfunction "PH2_F4") (pintype "passive"))
    )
    (net (code "20") (name "/CAN_S2") (class "Default")
      (node (ref "U18") (pin "G4") (pinfunction "PH3_G4") (pintype "passive"))
    )
    (net (code "21") (name "/CAN_S3") (class "Default")
      (node (ref "U18") (pin "H4") (pinfunction "PH4/I2C2_SCL_H4") (pintype "passive"))
    )
    (net (code "22") (name "/DRDY1") (class "Default")
      (node (ref "U18") (pin "A9") (pinfunction "PB4/SPI1_MISO/SPI3_MISO/SPI2_NSS/SPI6_MISO/CAN3_TX/UART7_TX_A9") (pintype "passive"))
    )
    (net (code "23") (name "/DRDY2") (class "Default")
      (node (ref "U18") (pin "R14") (pinfunction "PB14/USART1_TX/SPI2_MISO_R14") (pintype "passive"))
    )
    (net (code "24") (name "/DRDY3") (class "Default")
      (node (ref "U18") (pin "R15") (pinfunction "PB15/USART1_RX/SPI2_MOSI_R15") (pintype "passive"))
    )
    (net (code "25") (name "/DRDY4") (class "Default")
      (node (ref "U18") (pin "P5") (pinfunction "PC5/ADC1_IN15/ADC2_IN15_P5") (pintype "passive"))
    )
    (net (code "26") (name "/DRDY5") (class "Default")
      (node (ref "U18") (pin "D1") (pinfunction "PC13_D1") (pintype "passive"))
    )
    (net (code "27") (name "/DRDY6") (class "Default")
      (node (ref "U18") (pin "N15") (pinfunction "PD10_N15") (pintype "passive"))
    )
    (net (code "28") (name "/DRDY7") (class "Default")
      (node (ref "U18") (pin "L14") (pinfunction "PD15/TIM4_CH4_L14") (pintype "passive"))
    )
    (net (code "29") (name "/DRDY8") (class "Default")
      (node (ref "U18") (pin "R8") (pinfunction "PE7/UART7_RX_R8") (pintype "passive"))
    )
    (net (code "30") (name "/FMU_CAP1") (class "Default")
      (node (ref "U18") (pin "P4") (pinfunction "PA5/SPI1_SCK/SPI6_SCK_P4") (pintype "passive"))
    )
    (net (code "31") (name "/FMU_CAP2") (class "Default")
      (node (ref "U18") (pin "A10") (pinfunction "PB3/SPI1_SCK/SPI3_SCK/SPI6_SCK_A10") (pintype "passive"))
    )
    (net (code "32") (name "/FMU_CAP3") (class "Default")
      (node (ref "U18") (pin "R13") (pinfunction "PB11/I2C2_SDA/USART3_RX_R13") (pintype "passive"))
    )
    (net (code "33") (name "/FMU_CH1") (class "Default")
      (node (ref "U18") (pin "P11") (pinfunction "PE14/SPI4_MOSI_P11") (pintype "passive"))
    )
    (net (code "34") (name "/FMU_CH2") (class "Default")
      (node (ref "U18") (pin "D15") (pinfunction "PA10/USART1_RX_D15") (pintype "passive"))
    )
    (net (code "35") (name "/FMU_CH3") (class "Default")
      (node (ref "U18") (pin "P10") (pinfunction "PE11/SPI4_NSS_P10") (pintype "passive"))
    )
    (net (code "36") (name "/FMU_CH4") (class "Default")
      (node (ref "U18") (pin "P9") (pinfunction "PE9/TIM1_CH1_P9") (pintype "passive"))
    )
    (net (code "37") (name "/FMU_CH5") (class "Default")
      (node (ref "U18") (pin "M15") (pinfunction "PD13/I2C4_SDA_M15") (pintype "passive"))
    )
    (net (code "38") (name "/FMU_CH6") (class "Default")
      (node (ref "U18") (pin "M14") (pinfunction "PD14/TIM4_CH3_M14") (pintype "passive"))
    )
    (net (code "39") (name "/HEATER") (class "Default")
      (node (ref "R142") (pin "1") (pinfunction "1_1") (pintype "passive"))
      (node (ref "U18") (pin "R3") (pinfunction "PA7/SPI1_MOSI/SPI6_MOSI_R3") (pintype "passive"))
    )
    (net (code "40") (name "/HW_REV_DRIVE") (class "Default")
      (node (ref "U18") (pin "E13") (pinfunction "PH14/UART4_RX/CAN1_RX_E13") (pintype "passive"))
    )
    (net (code "41") (name "/HW_REV_SENSE") (class "Default")
      (node (ref "U18") (pin "M5") (pinfunction "PC3/SPI2_MOSI_M5") (pintype "passive"))
    )
    (net (code "42") (name "/HW_VER_DRIVE") (class "Default")
      (node (ref "U18") (pin "N7") (pinfunction "PG0_N7") (pintype "passive"))
    )
    (net (code "43") (name "/HW_VER_SENSE") (class "Default")
      (node (ref "U18") (pin "M4") (pinfunction "PC2/SPI2_MISO_M4") (pintype "passive"))
    )
    (net (code "44") (name "/I2C1_SCL_COMPASS") (class "Default")
      (node (ref "R129") (pin "1") (pinfunction "1_1") (pintype "passive"))
      (node (ref "R131") (pin "1") (pinfunction "1_1") (pintype "passive"))
      (node (ref "U18") (pin "A5") (pinfunction "PB8/I2C4_SCL/UART5_RX/CAN1_RX_A5") (pintype "passive"))
    )
    (net (code "45") (name "/I2C1_SDA_COMPASS") (class "Default")
      (node (ref "R128") (pin "1") (pinfunction "1_1") (pintype "passive"))
      (node (ref "R130") (pin "1") (pinfunction "1_1") (pintype "passive"))
      (node (ref "U18") (pin "B4") (pinfunction "PB9/I2C4_SDA/I2C1_SDA/SPI2_NSS/UART5_TX/CAN1_TX_B4") (pintype "passive"))
    )
    (net (code "46") (name "/I2C2_SCL_AIRSPEED") (class "Default")
      (node (ref "U18") (pin "H3") (pinfunction "PF1/I2C2_SCL_H3") (pintype "passive"))
    )
    (net (code "47") (name "/I2C2_SDA_AIRSPEED") (class "Default")
      (node (ref "U18") (pin "E2") (pinfunction "PF0/I2C2_SDA_E2") (pintype "passive"))
    )
    (net (code "48") (name "/I2C3_SCL") (class "Default")
      (node (ref "U18") (pin "N12") (pinfunction "PH7/I2C3_SCL/SPI5_MISO_N12") (pintype "passive"))
    )
    (net (code "49") (name "/I2C3_SDA") (class "Default")
      (node (ref "U18") (pin "M12") (pinfunction "PH8/I2C3_SDA_M12") (pintype "passive"))
    )
    (net (code "50") (name "/I2C4_SCL_EXTERNAL") (class "Default")
      (node (ref "U18") (pin "P7") (pinfunction "PF15/I2C4_SDA_P7") (pintype "passive"))
    )
    (net (code "51") (name "/I2C4_SDA_EXTERNAL") (class "Default")
      (node (ref "U18") (pin "R7") (pinfunction "PF14/I2C4_SCL_R7") (pintype "passive"))
    )
    (net (code "52") (name "/JTAG-SWCLK") (class "Default")
      (node (ref "R144") (pin "1") (pinfunction "1_1") (pintype "passive"))
      (node (ref "U18") (pin "A14") (pinfunction "PA14/JTCK-SWCLK_A14") (pintype "passive"))
    )
    (net (code "53") (name "/JTAG-SWDIO") (class "Default")
      (node (ref "R143") (pin "1") (pinfunction "1_1") (pintype "passive"))
      (node (ref "U18") (pin "A15") (pinfunction "PA13/JTMS-SWDIO_A15") (pintype "passive"))
    )
    (net (code "54") (name "/LED_BLUE") (class "Default")
      (node (ref "R157") (pin "2") (pinfunction "2_2") (pintype "passive"))
      (node (ref "U18") (pin "G15") (pinfunction "PC7/USART6_RX_G15") (pintype "passive"))
    )
    (net (code "55") (name "/LED_GREEN") (class "Default")
      (node (ref "R156") (pin "2") (pinfunction "2_2") (pintype "passive"))
      (node (ref "U18") (pin "H15") (pinfunction "PC6/USART6_TX_H15") (pintype "passive"))
    )
    (net (code "56") (name "/LED_RED") (class "Default")
      (node (ref "R154") (pin "2") (pinfunction "2_2") (pintype "passive"))
      (node (ref "U18") (pin "R4") (pinfunction "PB1/ADC1_IN9/ADC2_IN9_R4") (pintype "passive"))
    )
    (net (code "57") (name "/NRST") (class "Default")
      (node (ref "C88") (pin "1") (pinfunction "1_1") (pintype "passive"))
      (node (ref "J66") (pin "1") (pinfunction "1_1") (pintype "passive"))
      (node (ref "R161") (pin "1") (pinfunction "1_1") (pintype "passive"))
      (node (ref "U18") (pin "J1") (pinfunction "NRST_J1") (pintype "passive"))
    )
    (net (code "58") (name "/OSC32_IN") (class "Default")
      (node (ref "U18") (pin "E1") (pinfunction "PC14/OSC32_IN_E1") (pintype "passive"))
    )
    (net (code "59") (name "/OSC32_OUT") (class "Default")
      (node (ref "U18") (pin "F1") (pinfunction "PC15/OSC32_OUT_F1") (pintype "passive"))
    )
    (net (code "60") (name "/OSC_IN") (class "Default")
      (node (ref "C91") (pin "1") (pinfunction "1_1") (pintype "passive"))
      (node (ref "U18") (pin "G1") (pinfunction "PH0/OSC_IN_G1") (pintype "passive"))
      (node (ref "Y2") (pin "1") (pinfunction "I_1") (pintype "passive"))
    )
    (net (code "61") (name "/OSC_OUT") (class "Default")
      (node (ref "R169") (pin "1") (pinfunction "1_1") (pintype "passive"))
      (node (ref "U18") (pin "H1") (pinfunction "PH1/OSC_OUT_H1") (pintype "passive"))
    )
    (net (code "62") (name "/PDR_ON") (class "Default")
      (node (ref "J65") (pin "1") (pinfunction "1_1") (pintype "passive"))
      (node (ref "R160") (pin "1") (pinfunction "1_1") (pintype "passive"))
      (node (ref "U18") (pin "C6") (pinfunction "PDR_ON_C6") (pintype "passive"))
    )
    (net (code "63") (name "/POWER CONTROL") (class "Default")
      (node (ref "U18") (pin "B10") (pinfunction "PG10/SPI1_NSS_B10") (pintype "passive"))
    )
    (net (code "64") (name "/POWER_IN_A") (class "Default")
      (node (ref "R172") (pin "2") (pinfunction "2_2") (pintype "passive"))
      (node (ref "U18") (pin "M7") (pinfunction "PG1_M7") (pintype "passive"))
    )
    (net (code "65") (name "/POWER_IN_B") (class "Default")
      (node (ref "R171") (pin "2") (pinfunction "2_2") (pintype "passive"))
      (node (ref "U18") (pin "L15") (pinfunction "PG2_L15") (pintype "passive"))
    )
    (net (code "66") (name "/POWER_IN_B_KEY Detect") (class "Default")
      (node (ref "U18") (pin "N6") (pinfunction "PF13_N6") (pintype "passive"))
    )
    (net (code "67") (name "/POWER_IN_C") (class "Default")
      (node (ref "R170") (pin "2") (pinfunction "2_2") (pintype "passive"))
      (node (ref "U18") (pin "K15") (pinfunction "PG3_K15") (pintype "passive"))
    )
    (net (code "68") (name "/PPM_IN") (class "Default")
      (node (ref "U18") (pin "C4") (pinfunction "PI5_C4") (pintype "passive"))
    )
    (net (code "69") (name "/RSSI") (class "Default")
      (node (ref "U18") (pin "R5") (pinfunction "PB0/ADC1_IN8/ADC2_IN8_R5") (pintype "passive"))
    )
    (net (code "70") (name "/SBUS") (class "Default")
      (node (ref "U18") (pin "D13") (pinfunction "PH15_D13") (pintype "passive"))
    )
    (net (code "71") (name "/SCALED_V3V3") (class "Default")
      (node (ref "R174") (pin "2") (pinfunction "2_2") (pintype "passive"))
      (node (ref "R177") (pin "1") (pinfunction "1_1") (pintype "passive"))
      (node (ref "U18") (pin "M3") (pinfunction "PC1/SPI2_MOSI_M3") (pintype "passive"))
    )
    (net (code "72") (name "/SCALED_V5") (class "Default")
      (node (ref "R173") (pin "2") (pinfunction "2_2") (pintype "passive"))
      (node (ref "R176") (pin "1") (pinfunction "1_1") (pintype "passive"))
      (node (ref "U18") (pin "M2") (pinfunction "PC0_M2") (pintype "passive"))
    )
    (net (code "73") (name "/SDMMC1_CLK") (class "Default")
      (node (ref "R123") (pin "1") (pinfunction "1_1") (pintype "passive"))
      (node (ref "U18") (pin "A12") (pinfunction "PC12/SPI3_MOSI/UART5_TX_A12") (pintype "passive"))
    )
    (net (code "74") (name "/SDMMC1_CMD") (class "Default")
      (node (ref "R121") (pin "1") (pinfunction "1_1") (pintype "passive"))
      (node (ref "U18") (pin "D12") (pinfunction "PD2/UART5_RX/SDMMC1_CMD_D12") (pintype "passive"))
    )
    (net (code "75") (name "/SDMMC1_D0") (class "Default")
      (node (ref "R126") (pin "1") (pinfunction "1_1") (pintype "passive"))
      (node (ref "U18") (pin "G14") (pinfunction "PC8/SDMMC1_D0_G14") (pintype "passive"))
    )
    (net (code "76") (name "/SDMMC1_D1") (class "Default")
      (node (ref "R127") (pin "1") (pinfunction "1_1") (pintype "passive"))
      (node (ref "U18") (pin "F14") (pinfunction "PC9/I2C3_SDA/SDMMC1_D1_F14") (pintype "passive"))
    )
    (net (code "77") (name "/SDMMC1_D2") (class "Default")
      (node (ref "R117") (pin "1") (pinfunction "1_1") (pintype "passive"))
      (node (ref "U18") (pin "B14") (pinfunction "PC10/SPI3_SCK/USART3_TX/UART4_TX_B14") (pintype "passive"))
    )
    (net (code "78") (name "/SDMMC1_D3") (class "Default")
      (node (ref "R119") (pin "1") (pinfunction "1_1") (pintype "passive"))
      (node (ref "U18") (pin "B13") (pinfunction "PC11/SPI3_MISO/USART3_RX/UART4_RX_B13") (pintype "passive"))
    )
    (net (code "79") (name "/SPEKTRUM_POWER") (class "Default")
      (node (ref "U18") (pin "B1") (pinfunction "PE4/SPI4_NSS_B1") (pintype "passive"))
    )
    (net (code "80") (name "/SPI1_CS1") (class "Default")
      (node (ref "R132") (pin "1") (pinfunction "1_1") (pintype "passive"))
      (node (ref "U18") (pin "H2") (pinfunction "PF2_H2") (pintype "passive"))
    )
    (net (code "81") (name "/SPI1_CS2") (class "Default")
      (node (ref "U18") (pin "J2") (pinfunction "PF3_J2") (pintype "passive"))
    )
    (net (code "82") (name "/SPI1_CS3") (class "Default")
      (node (ref "U18") (pin "J3") (pinfunction "PF4_J3") (pintype "passive"))
    )
    (net (code "83") (name "/SPI1_MISO_SENSOR1") (class "Default")
      (node (ref "R137") (pin "1") (pinfunction "1_1") (pintype "passive"))
      (node (ref "U18") (pin "P3") (pinfunction "PA6/SPI1_MISO/SPI6_MISO_P3") (pintype "passive"))
    )
    (net (code "84") (name "/SPI1_MOSI_SENSOR1") (class "Default")
      (node (ref "R134") (pin "1") (pinfunction "1_1") (pintype "passive"))
      (node (ref "U18") (pin "A11") (pinfunction "PD7/SPI1_MOSI_A11") (pintype "passive"))
    )
    (net (code "85") (name "/SPI1_SCK_SENSOR1") (class "Default")
      (node (ref "R133") (pin "1") (pinfunction "1_1") (pintype "passive"))
      (node (ref "U18") (pin "B9") (pinfunction "PG11/SPI1_SCK_B9") (pintype "passive"))
    )
    (net (code "86") (name "/SPI2_CS_FRAM") (class "Default")
      (node (ref "J61") (pin "1") (pinfunction "1_1") (pintype "passive"))
      (node (ref "U17") (pin "1") (pinfunction "~{CS}_1") (pintype "passive"))
      (node (ref "U18") (pin "K3") (pinfunction "PF5_K3") (pintype "passive"))
    )
    (net (code "87") (name "/SPI2_MISO_FRAM") (class "Default")
      (node (ref "J62") (pin "1") (pinfunction "1_1") (pintype "passive"))
      (node (ref "U17") (pin "2") (pinfunction "SO_2") (pintype "passive"))
      (node (ref "U18") (pin "C14") (pinfunction "PI2/SPI2_MISO_C14") (pintype "passive"))
    )
    (net (code "88") (name "/SPI2_MOSI_FRAM") (class "Default")
      (node (ref "J63") (pin "1") (pinfunction "1_1") (pintype "passive"))
      (node (ref "U17") (pin "5") (pinfunction "SI_5") (pintype "passive"))
      (node (ref "U18") (pin "C13") (pinfunction "PI3/SPI2_MOSI_C13") (pintype "passive"))
    )
    (net (code "89") (name "/SPI2_SCK_FRAM") (class "Default")
      (node (ref "J64") (pin "1") (pinfunction "1_1") (pintype "passive"))
      (node (ref "U17") (pin "6") (pinfunction "SCK_6") (pintype "passive"))
      (node (ref "U18") (pin "D14") (pinfunction "PI1/SPI2_SCK_D14") (pintype "passive"))
    )
    (net (code "90") (name "/SPI4_CS1") (class "Default")
      (node (ref "R145") (pin "1") (pinfunction "1_1") (pintype "passive"))
      (node (ref "U18") (pin "L1") (pinfunction "PF10_L1") (pintype "passive"))
    )
    (net (code "91") (name "/SPI4_CS2") (class "Default")
      (node (ref "U18") (pin "R6") (pinfunction "PF11/SPI5_MOSI_R6") (pintype "passive"))
    )
    (net (code "92") (name "/SPI4_CS3") (class "Default")
      (node (ref "U18") (pin "P6") (pinfunction "PF12_P6") (pintype "passive"))
    )
    (net (code "93") (name "/SPI4_MISO_SENSOR2") (class "Default")
      (node (ref "R150") (pin "1") (pinfunction "1_1") (pintype "passive"))
      (node (ref "U18") (pin "N11") (pinfunction "PE13/SPI4_MISO_N11") (pintype "passive"))
    )
    (net (code "94") (name "/SPI4_MOSI_SENSOR2") (class "Default")
      (node (ref "R147") (pin "1") (pinfunction "1_1") (pintype "passive"))
      (node (ref "U18") (pin "B3") (pinfunction "PE6/SPI4_MOSI_B3") (pintype "passive"))
    )
    (net (code "95") (name "/SPI4_SCK_SENSOR2") (class "Default")
      (node (ref "R146") (pin "1") (pinfunction "1_1") (pintype "passive"))
      (node (ref "U18") (pin "A2") (pinfunction "PE2/SPI4_SCK_A2") (pintype "passive"))
    )
    (net (code "96") (name "/SPI5_MISO_EXTERNAL1") (class "Default")
      (node (ref "U18") (pin "L3") (pinfunction "PF8/SPI5_MISO_L3") (pintype "passive"))
    )
    (net (code "97") (name "/SPI5_MOSI_EXTERNAL1") (class "Default")
      (node (ref "U18") (pin "L2") (pinfunction "PF9/SPI5_MOSI_L2") (pintype "passive"))
    )
    (net (code "98") (name "/SPI5_SCK_EXTERNAL1") (class "Default")
      (node (ref "U18") (pin "K1") (pinfunction "PF7/SPI5_SCK/UART7_TX_K1") (pintype "passive"))
    )
    (net (code "99") (name "/SPI6_CS1_EXTERNAL1") (class "Default")
      (node (ref "U18") (pin "D4") (pinfunction "PI4_D4") (pintype "passive"))
    )
    (net (code "100") (name "/SPI6_CS1_EXTERNAL2") (class "Default")
      (node (ref "U18") (pin "C3") (pinfunction "PI6_C3") (pintype "passive"))
    )
    (net (code "101") (name "/SPI6_CS2_EXTERNAL2") (class "Default")
      (node (ref "U18") (pin "C2") (pinfunction "PI7_C2") (pintype "passive"))
    )
    (net (code "102") (name "/SPI6_CS3_EXTERNAL2") (class "Default")
      (node (ref "U18") (pin "D2") (pinfunction "PI8_D2") (pintype "passive"))
    )
    (net (code "103") (name "/SPI6_EXTERNAL1_CS2") (class "Default")
      (node (ref "U18") (pin "E3") (pinfunction "PI10_E3") (pintype "passive"))
    )
    (net (code "104") (name "/SPI6_EXTERNAL1_CS3") (class "Default")
      (node (ref "U18") (pin "E4") (pinfunction "PI11_E4") (pintype "passive"))
    )
    (net (code "105") (name "/SPI6_MISO_EXTERNAL2") (class "Default")
      (node (ref "U18") (pin "B8") (pinfunction "PG12/SPI6_MISO_B8") (pintype "passive"))
    )
    (net (code "106") (name "/SPI6_MOSI_EXTERNAL2") (class "Default")
      (node (ref "U18") (pin "A6") (pinfunction "PB5/UART5_RX/SPI1_MOSI/SPI3_MOSI/SPI6_MOSI/CAN2_RX_A6") (pintype "passive"))
    )
    (net (code "107") (name "/SPI6_SCK_EXTERNAL2") (class "Default")
      (node (ref "U18") (pin "A8") (pinfunction "PG13/SPI6_SCK_A8") (pintype "passive"))
    )
    (net (code "108") (name "/SPIAUX_MEM_CS") (class "Default")
      (node (ref "U18") (pin "J4") (pinfunction "PH5/I2C2_SDA_J4") (pintype "passive"))
    )
    (net (code "109") (name "/SWITCH") (class "Default")
      (node (ref "J10") (pin "5") (pinfunction "5_5") (pintype "passive"))
    )
    (net (code "110") (name "/TIM5_SPARE_4") (class "Default")
      (node (ref "U18") (pin "E14") (pinfunction "PI0/SPI2_NSS_E14") (pintype "passive"))
    )
    (net (code "111") (name "/TIM9_SPARE_1") (class "Default")
      (node (ref "U18") (pin "B2") (pinfunction "PE5/SPI4_MISO_B2") (pintype "passive"))
    )
    (net (code "112") (name "/UART2_RX_TOF") (class "Default")
      (node (ref "R148") (pin "1") (pinfunction "1_1") (pintype "passive"))
      (node (ref "U18") (pin "B11") (pinfunction "PD6/SPI3_MOSI/USART2_RX_B11") (pintype "passive"))
    )
    (net (code "113") (name "/UART2_TX_TOF") (class "Default")
      (node (ref "R149") (pin "1") (pinfunction "1_1") (pintype "passive"))
      (node (ref "U18") (pin "C11") (pinfunction "PD5/USART2_TX_C11") (pintype "passive"))
    )
    (net (code "114") (name "/UART4_RX_Gimbal") (class "Default")
      (node (ref "R139") (pin "1") (pinfunction "1_1") (pintype "passive"))
      (node (ref "U18") (pin "B12") (pinfunction "PD0/UART4_RX/CAN1_RX_B12") (pintype "passive"))
    )
    (net (code "115") (name "/UART4_TX_Gimbal") (class "Default")
      (node (ref "R140") (pin "1") (pinfunction "1_1") (pintype "passive"))
      (node (ref "U18") (pin "C12") (pinfunction "PD1/UART4_TX/CAN1_TX_C12") (pintype "passive"))
    )
    (net (code "116") (name "/UART7_RX_Battery") (class "Default")
      (node (ref "U18") (pin "K2") (pinfunction "PF6/SPI5_NSS/UART7_RX_K2") (pintype "passive"))
    )
    (net (code "117") (name "/UART7_TX_Battery") (class "Default")
      (node (ref "U18") (pin "P8") (pinfunction "PE8/UART7_TX_P8") (pintype "passive"))
    )
    (net (code "118") (name "/UART8_RX_DEBUG") (class "Default")
      (node (ref "R141") (pin "1") (pinfunction "1_1") (pintype "passive"))
      (node (ref "U18") (pin "A4") (pinfunction "PE0/UART8_RX_A4") (pintype "passive"))
    )
    (net (code "119") (name "/UART8_TX_DEBUG") (class "Default")
      (node (ref "R138") (pin "1") (pinfunction "1_1") (pintype "passive"))
      (node (ref "U18") (pin "A3") (pinfunction "PE1/UART8_TX_A3") (pintype "passive"))
    )
    (net (code "120") (name "/USART1_RX_GPS") (class "Default")
      (node (ref "R118") (pin "1") (pinfunction "1_1") (pintype "passive"))
      (node (ref "U18") (pin "B5") (pinfunction "PB7/I2C1_SDA/USART1_RX/I2C4_SDA_B5") (pintype "passive"))
    )
    (net (code "121") (name "/USART1_TX_GPS") (class "Default")
      (node (ref "R125") (pin "1") (pinfunction "1_1") (pintype "passive"))
      (node (ref "U18") (pin "B6") (pinfunction "PB6/UART5_TX/I2C1_SCL/USART1_TX/CAN2_TX/I2C4_SCL_B6") (pintype "passive"))
    )
    (net (code "122") (name "/USART2_CTS_TELEM1") (class "Default")
      (node (ref "U18") (pin "D11") (pinfunction "PD3/SPI2_SCK/USART2_CTS_D11") (pintype "passive"))
    )
    (net (code "123") (name "/USART2_RTS_TELEM1") (class "Default")
      (node (ref "U18") (pin "D10") (pinfunction "PD4/USART2_RTS_D10") (pintype "passive"))
    )
    (net (code "124") (name "/USART3_CTS_TELEM2") (class "Default")
      (node (ref "U18") (pin "N14") (pinfunction "PD11/USART3_CTS_N14") (pintype "passive"))
    )
    (net (code "125") (name "/USART3_RTS_TELEM2") (class "Default")
      (node (ref "U18") (pin "N13") (pinfunction "PD12/I2C4_SCL/USART3_RTS_N13") (pintype "passive"))
    )
    (net (code "126") (name "/USART3_RX_A9") (class "Default")
      (node (ref "R135") (pin "1") (pinfunction "1_1") (pintype "passive"))
      (node (ref "U18") (pin "P14") (pinfunction "PD9/USART3_RX_P14") (pintype "passive"))
    )
    (net (code "127") (name "/USART3_TX_A9") (class "Default")
      (node (ref "R136") (pin "1") (pinfunction "1_1") (pintype "passive"))
      (node (ref "U18") (pin "P15") (pinfunction "PD8/USART3_TX_P15") (pintype "passive"))
    )
    (net (code "128") (name "/USART6_CTS_TELEM3") (class "Default")
      (node (ref "U18") (pin "B7") (pinfunction "PG15/USART6_CTS_B7") (pintype "passive"))
    )
    (net (code "129") (name "/USART6_RTS_TELEM3") (class "Default")
      (node (ref "U18") (pin "H14") (pinfunction "PG8/SPI6_NSS_H14") (pintype "passive"))
    )
    (net (code "130") (name "/USART6_RX_TELEM3") (class "Default")
      (node (ref "R151") (pin "1") (pinfunction "1_1") (pintype "passive"))
      (node (ref "U18") (pin "C10") (pinfunction "PG9/SPI1_MISO/USART6_RX_C10") (pintype "passive"))
    )
    (net (code "131") (name "/USART6_TX_TELEM3") (class "Default")
      (node (ref "R152") (pin "1") (pinfunction "1_1") (pintype "passive"))
      (node (ref "U18") (pin "A7") (pinfunction "PG14/SPI6_MOSI/USART6_TX_A7") (pintype "passive"))
    )
    (net (code "132") (name "/USB_DM") (class "Default")
      (node (ref "R120") (pin "1") (pinfunction "1_1") (pintype "passive"))
      (node (ref "U18") (pin "C15") (pinfunction "PA11/SPI2_NSS/UART4_RX/CAN1_RX_C15") (pintype "passive"))
    )
    (net (code "133") (name "/USB_DP") (class "Default")
      (node (ref "R122") (pin "1") (pinfunction "1_1") (pintype "passive"))
      (node (ref "U18") (pin "B15") (pinfunction "PA12/SPI2_SCK/UART4_TX/CAN1_TX_B15") (pintype "passive"))
    )
    (net (code "134") (name "/USER_BUTTON") (class "Default")
      (node (ref "U18") (pin "R9") (pinfunction "PE10_R9") (pintype "passive"))
    )
    (net (code "135") (name "/USER_LED") (class "Default")
      (node (ref "U18") (pin "R10") (pinfunction "PE12/SPI4_SCK_R10") (pintype "passive"))
    )
    (net (code "136") (name "/USER_LED_B") (class "Default")
      (node (ref "Q12") (pin "2") (pinfunction "B1_2") (pintype "passive"))
      (node (ref "U18") (pin "K12") (pinfunction "PH12/I2C4_SDA_K12") (pintype "passive"))
    )
    (net (code "137") (name "/USER_LED_G") (class "Default")
      (node (ref "Q11") (pin "2") (pinfunction "B1_2") (pintype "passive"))
      (node (ref "U18") (pin "L12") (pinfunction "PH11/I2C4_SCL_L12") (pintype "passive"))
    )
    (net (code "138") (name "/USER_LED_R") (class "Default")
      (node (ref "Q11") (pin "5") (pinfunction "B2_5") (pintype "passive"))
      (node (ref "U18") (pin "L13") (pinfunction "PH10_L13") (pintype "passive"))
    )
    (net (code "139") (name "/VBUS") (class "Default")
      (node (ref "R124") (pin "1") (pinfunction "1_1") (pintype "passive"))
      (node (ref "U18") (pin "E15") (pinfunction "PA9/SPI2_SCK/USART1_TX_E15") (pintype "passive"))
    )
    (net (code "140") (name "/VDD_3V3V_RC_EN") (class "Default")
      (node (ref "U18") (pin "K13") (pinfunction "PG5_K13") (pintype "passive"))
    )
    (net (code "141") (name "/VDD_3V3V_SD_CARD_EN") (class "Default")
      (node (ref "U18") (pin "J14") (pinfunction "PG7_J14") (pintype "passive"))
    )
    (net (code "142") (name "/VDD_3V3V_SENSORS_EN") (class "Default")
      (node (ref "U18") (pin "A1") (pinfunction "PE3_A1") (pintype "passive"))
    )
    (net (code "143") (name "/VDD_5V_PERIPH_EN") (class "Default")
      (node (ref "U18") (pin "K14") (pinfunction "PG4_K14") (pintype "passive"))
    )
    (net (code "144") (name "/VDD_5V_PERIPH_OC") (class "Default")
      (node (ref "U18") (pin "R11") (pinfunction "PE15_R11") (pintype "passive"))
    )
    (net (code "145") (name "/VDD_5V_WIFI_EN") (class "Default")
      (node (ref "U18") (pin "J15") (pinfunction "PG6_J15") (pintype "passive"))
    )
    (net (code "146") (name "/VDD_BRICK_VALID") (class "Default")
      (node (ref "R164") (pin "2") (pinfunction "2_2") (pintype "passive"))
      (node (ref "U18") (pin "R12") (pinfunction "PB10/I2C2_SCL/SPI2_SCK/USART3_TX_R12") (pintype "passive"))
    )
    (net (code "147") (name "GND") (class "Default")
      (node (ref "C49") (pin "2") (pinfunction "2_2") (pintype "passive"))
      (node (ref "C50") (pin "2") (pinfunction "2_2") (pintype "passive"))
      (node (ref "C51") (pin "2") (pinfunction "2_2") (pintype "passive"))
      (node (ref "C52") (pin "2") (pinfunction "2_2") (pintype "passive"))
      (node (ref "C53") (pin "2") (pinfunction "2_2") (pintype "passive"))
      (node (ref "C54") (pin "2") (pinfunction "2_2") (pintype "passive"))
      (node (ref "C55") (pin "2") (pinfunction "2_2") (pintype "passive"))
      (node (ref "C56") (pin "2") (pinfunction "2_2") (pintype "passive"))
      (node (ref "C57") (pin "2") (pinfunction "2_2") (pintype "passive"))
      (node (ref "C58") (pin "2") (pinfunction "2_2") (pintype "passive"))
      (node (ref "C59") (pin "2") (pinfunction "2_2") (pintype "passive"))
      (node (ref "C60") (pin "2") (pinfunction "2_2") (pintype "passive"))
      (node (ref "C61") (pin "2") (pinfunction "2_2") (pintype "passive"))
      (node (ref "C62") (pin "2") (pinfunction "2_2") (pintype "passive"))
      (node (ref "C63") (pin "2") (pinfunction "2_2") (pintype "passive"))
      (node (ref "C64") (pin "2") (pinfunction "2_2") (pintype "passive"))
      (node (ref "C65") (pin "2") (pinfunction "2_2") (pintype "passive"))
      (node (ref "C66") (pin "2") (pinfunction "2_2") (pintype "passive"))
      (node (ref "C67") (pin "2") (pinfunction "2_2") (pintype "passive"))
      (node (ref "C68") (pin "2") (pinfunction "2_2") (pintype "passive"))
      (node (ref "C69") (pin "2") (pinfunction "2_2") (pintype "passive"))
      (node (ref "C70") (pin "2") (pinfunction "2_2") (pintype "passive"))
      (node (ref "C71") (pin "2") (pinfunction "2_2") (pintype "passive"))
      (node (ref "C72") (pin "2") (pinfunction "2_2") (pintype "passive"))
      (node (ref "C73") (pin "2") (pinfunction "2_2") (pintype "passive"))
      (node (ref "C74") (pin "2") (pinfunction "2_2") (pintype "passive"))
      (node (ref "C75") (pin "2") (pinfunction "2_2") (pintype "passive"))
      (node (ref "C76") (pin "2") (pinfunction "2_2") (pintype "passive"))
      (node (ref "C77") (pin "2") (pinfunction "2_2") (pintype "passive"))
      (node (ref "C78") (pin "2") (pinfunction "2_2") (pintype "passive"))
      (node (ref "C79") (pin "2") (pinfunction "2_2") (pintype "passive"))
      (node (ref "C80") (pin "2") (pinfunction "2_2") (pintype "passive"))
      (node (ref "C81") (pin "2") (pinfunction "2_2") (pintype "passive"))
      (node (ref "C82") (pin "2") (pinfunction "2_2") (pintype "passive"))
      (node (ref "C83") (pin "2") (pinfunction "2_2") (pintype "passive"))
      (node (ref "C84") (pin "2") (pinfunction "2_2") (pintype "passive"))
      (node (ref "C85") (pin "2") (pinfunction "2_2") (pintype "passive"))
      (node (ref "C86") (pin "2") (pinfunction "2_2") (pintype "passive"))
      (node (ref "C88") (pin "2") (pinfunction "2_2") (pintype "passive"))
      (node (ref "C91") (pin "2") (pinfunction "2_2") (pintype "passive"))
      (node (ref "C92") (pin "2") (pinfunction "2_2") (pintype "passive"))
      (node (ref "D1") (pin "1") (pinfunction "1_1") (pintype "passive"))
      (node (ref "D2") (pin "1") (pinfunction "1_1") (pintype "passive"))
      (node (ref "D4") (pin "1") (pinfunction "1_1") (pintype "passive"))
      (node (ref "J10") (pin "6") (pinfunction "6_6") (pintype "passive"))
      (node (ref "J10") (pin "7") (pinfunction "7_7") (pintype "passive"))
      (node (ref "J10") (pin "8") (pinfunction "8_8") (pintype "passive"))
      (node (ref "J12") (pin "5") (pinfunction "GND_5") (pintype "passive"))
      (node (ref "J12") (pin "6") (pinfunction "GND_6") (pintype "passive"))
      (node (ref "J12") (pin "7") (pinfunction "GND_7") (pintype "passive"))
      (node (ref "J13") (pin "10") (pinfunction "10_10") (pintype "passive"))
      (node (ref "J13") (pin "11") (pinfunction "11_11") (pintype "passive"))
      (node (ref "J13") (pin "12") (pinfunction "12_12") (pintype "passive"))
      (node (ref "J13") (pin "13") (pinfunction "13_13") (pintype "passive"))
      (node (ref "J13") (pin "6") (pinfunction "6_6") (pintype "passive"))
      (node (ref "J13") (pin "9") (pinfunction "9_9") (pintype "passive"))
      (node (ref "J17") (pin "16") (pinfunction "16_16") (pintype "passive"))
      (node (ref "J17") (pin "5") (pinfunction "5_5") (pintype "passive"))
      (node (ref "J18") (pin "1") (pinfunction "1_1") (pintype "passive"))
      (node (ref "J18") (pin "5") (pinfunction "5_5") (pintype "passive"))
      (node (ref "J18") (pin "6") (pinfunction "6_6") (pintype "passive"))
      (node (ref "J28") (pin "1") (pinfunction "1_1") (pintype "passive"))
      (node (ref "J33") (pin "1") (pinfunction "1_1") (pintype "passive"))
      (node (ref "J35") (pin "1") (pinfunction "1_1") (pintype "passive"))
      (node (ref "J40") (pin "5") (pinfunction "5_5") (pintype "passive"))
      (node (ref "J40") (pin "6") (pinfunction "6_6") (pintype "passive"))
      (node (ref "J40") (pin "7") (pinfunction "7_7") (pintype "passive"))
      (node (ref "J40") (pin "8") (pinfunction "8_8") (pintype "passive"))
      (node (ref "J43") (pin "4") (pinfunction "4_4") (pintype "passive"))
      (node (ref "J43") (pin "5") (pinfunction "5_5") (pintype "passive"))
      (node (ref "J43") (pin "6") (pinfunction "6_6") (pintype "passive"))
      (node (ref "J44") (pin "6") (pinfunction "6_6") (pintype "passive"))
      (node (ref "J50") (pin "1") (pinfunction "1_1") (pintype "passive"))
      (node (ref "J55") (pin "1") (pinfunction "1_1") (pintype "passive"))
      (node (ref "J57") (pin "4") (pinfunction "4_4") (pintype "passive"))
      (node (ref "J57") (pin "5") (pinfunction "5_5") (pintype "passive"))
      (node (ref "J57") (pin "6") (pinfunction "6_6") (pintype "passive"))
      (node (ref "J58") (pin "4") (pinfunction "4_4") (pintype "passive"))
      (node (ref "J58") (pin "5") (pinfunction "5_5") (pintype "passive"))
      (node (ref "J58") (pin "6") (pinfunction "6_6") (pintype "passive"))
      (node (ref "Q11") (pin "1") (pinfunction "E1_1") (pintype "passive"))
      (node (ref "Q11") (pin "4") (pinfunction "E2_4") (pintype "passive"))
      (node (ref "Q12") (pin "1") (pinfunction "E1_1") (pintype "passive"))
      (node (ref "Q12") (pin "4") (pinfunction "E2_4") (pintype "passive"))
      (node (ref "R158") (pin "1") (pinfunction "1_1") (pintype "passive"))
      (node (ref "R162") (pin "1") (pinfunction "1_1") (pintype "passive"))
      (node (ref "R176") (pin "2") (pinfunction "2_2") (pintype "passive"))
      (node (ref "R177") (pin "2") (pinfunction "2_2") (pintype "passive"))
      (node (ref "R178") (pin "2") (pinfunction "2_2") (pintype "passive"))
      (node (ref "U17") (pin "4") (pinfunction "VSS_4") (pintype "passive"))
      (node (ref "U18") (pin "D5") (pinfunction "VSS_D5") (pintype "passive"))
      (node (ref "U18") (pin "D7") (pinfunction "VSS_D7") (pintype "passive"))
      (node (ref "U18") (pin "D8") (pinfunction "VSS_D8") (pintype "passive"))
      (node (ref "U18") (pin "D9") (pinfunction "VSS_D9") (pintype "passive"))
      (node (ref "U18") (pin "F12") (pinfunction "VSS_F12") (pintype "passive"))
      (node (ref "U18") (pin "F2") (pinfunction "VSS_F2") (pintype "passive"))
      (node (ref "U18") (pin "G12") (pinfunction "VSS_G12") (pintype "passive"))
      (node (ref "U18") (pin "G2") (pinfunction "VSS_G2") (pintype "passive"))
      (node (ref "U18") (pin "H12") (pinfunction "VSS_H12") (pintype "passive"))
      (node (ref "U18") (pin "M1") (pinfunction "VSSA_M1") (pintype "passive"))
      (node (ref "U18") (pin "M8") (pinfunction "VSS_M8") (pintype "passive"))
      (node (ref "U18") (pin "M9") (pinfunction "VSS_M9") (pintype "passive"))
      (node (ref "U18") (pin "N1") (pinfunction "VREF-_N1") (pintype "passive"))
      (node (ref "Y2") (pin "2") (pinfunction "G_2") (pintype "passive"))
      (node (ref "Y2") (pin "4") (pinfunction "G_4") (pintype "passive"))
    )
    (net (code "148") (name "Net-(D3-A)") (class "Default")
      (node (ref "C50") (pin "1") (pinfunction "1_1") (pintype "passive"))
      (node (ref "D3") (pin "1") (pinfunction "A_1") (pintype "passive"))
      (node (ref "D4") (pin "2") (pinfunction "2_2") (pintype "passive"))
      (node (ref "J12") (pin "1") (pinfunction "VBUS_1") (pintype "passive"))
      (node (ref "R124") (pin "2") (pinfunction "2_2") (pintype "passive"))
    )
    (net (code "149") (name "Net-(D5-K)") (class "Default")
      (node (ref "D5") (pin "2") (pinfunction "K_2") (pintype "passive"))
      (node (ref "R154") (pin "1") (pinfunction "1_1") (pintype "passive"))
    )
    (net (code "150") (name "Net-(D6-K)") (class "Default")
      (node (ref "D6") (pin "2") (pinfunction "K_2") (pintype "passive"))
      (node (ref "R156") (pin "1") (pinfunction "1_1") (pintype "passive"))
    )
    (net (code "151") (name "Net-(D7-K)") (class "Default")
      (node (ref "D7") (pin "2") (pinfunction "K_2") (pintype "passive"))
      (node (ref "R157") (pin "1") (pinfunction "1_1") (pintype "passive"))
    )
    (net (code "152") (name "Net-(J10-Pad4)") (class "Default")
      (node (ref "J10") (pin "4") (pinfunction "4_4") (pintype "passive"))
      (node (ref "R116") (pin "1") (pinfunction "1_1") (pintype "passive"))
    )
    (net (code "153") (name "Net-(J12-DM)") (class "Default")
      (node (ref "D2") (pin "2") (pinfunction "2_2") (pintype "passive"))
      (node (ref "J12") (pin "2") (pinfunction "DM_2") (pintype "passive"))
      (node (ref "R120") (pin "2") (pinfunction "2_2") (pintype "passive"))
    )
    (net (code "154") (name "Net-(J12-DP)") (class "Default")
      (node (ref "D1") (pin "2") (pinfunction "2_2") (pintype "passive"))
      (node (ref "J12") (pin "3") (pinfunction "DP_3") (pintype "passive"))
      (node (ref "R122") (pin "2") (pinfunction "2_2") (pintype "passive"))
    )
    (net (code "155") (name "Net-(J13-Pad1)") (class "Default")
      (node (ref "J13") (pin "1") (pinfunction "1_1") (pintype "passive"))
      (node (ref "J7") (pin "1") (pinfunction "1_1") (pintype "passive"))
      (node (ref "R111") (pin "2") (pinfunction "2_2") (pintype "passive"))
      (node (ref "R117") (pin "2") (pinfunction "2_2") (pintype "passive"))
    )
    (net (code "156") (name "Net-(J13-Pad2)") (class "Default")
      (node (ref "J13") (pin "2") (pinfunction "2_2") (pintype "passive"))
      (node (ref "J8") (pin "1") (pinfunction "1_1") (pintype "passive"))
      (node (ref "R112") (pin "2") (pinfunction "2_2") (pintype "passive"))
      (node (ref "R119") (pin "2") (pinfunction "2_2") (pintype "passive"))
    )
    (net (code "157") (name "Net-(J13-Pad3)") (class "Default")
      (node (ref "J13") (pin "3") (pinfunction "3_3") (pintype "passive"))
      (node (ref "J9") (pin "1") (pinfunction "1_1") (pintype "passive"))
      (node (ref "R113") (pin "2") (pinfunction "2_2") (pintype "passive"))
      (node (ref "R121") (pin "2") (pinfunction "2_2") (pintype "passive"))
    )
    (net (code "158") (name "Net-(J13-Pad5)") (class "Default")
      (node (ref "J13") (pin "5") (pinfunction "5_5") (pintype "passive"))
      (node (ref "J20") (pin "1") (pinfunction "1_1") (pintype "passive"))
      (node (ref "R123") (pin "2") (pinfunction "2_2") (pintype "passive"))
    )
    (net (code "159") (name "Net-(J13-Pad7)") (class "Default")
      (node (ref "J13") (pin "7") (pinfunction "7_7") (pintype "passive"))
      (node (ref "J21") (pin "1") (pinfunction "1_1") (pintype "passive"))
      (node (ref "R114") (pin "2") (pinfunction "2_2") (pintype "passive"))
      (node (ref "R126") (pin "2") (pinfunction "2_2") (pintype "passive"))
    )
    (net (code "160") (name "Net-(J13-Pad8)") (class "Default")
      (node (ref "J13") (pin "8") (pinfunction "8_8") (pintype "passive"))
      (node (ref "J22") (pin "1") (pinfunction "1_1") (pintype "passive"))
      (node (ref "R115") (pin "2") (pinfunction "2_2") (pintype "passive"))
      (node (ref "R127") (pin "2") (pinfunction "2_2") (pintype "passive"))
    )
    (net (code "161") (name "Net-(J14-Pad1)") (class "Default")
      (node (ref "J14") (pin "1") (pinfunction "1_1") (pintype "passive"))
      (node (ref "J17") (pin "1") (pinfunction "1_1") (pintype "passive"))
      (node (ref "R118") (pin "2") (pinfunction "2_2") (pintype "passive"))
    )
    (net (code "162") (name "Net-(J15-Pad1)") (class "Default")
      (node (ref "J15") (pin "1") (pinfunction "1_1") (pintype "passive"))
      (node (ref "J17") (pin "2") (pinfunction "2_2") (pintype "passive"))
      (node (ref "R125") (pin "2") (pinfunction "2_2") (pintype "passive"))
    )
    (net (code "163") (name "Net-(J16-Pad1)") (class "Default")
      (node (ref "J16") (pin "1") (pinfunction "1_1") (pintype "passive"))
      (node (ref "J17") (pin "3") (pinfunction "3_3") (pintype "passive"))
      (node (ref "R128") (pin "2") (pinfunction "2_2") (pintype "passive"))
    )
    (net (code "164") (name "Net-(J17-Pad6)") (class "Default")
      (node (ref "J17") (pin "6") (pinfunction "6_6") (pintype "passive"))
      (node (ref "J19") (pin "1") (pinfunction "1_1") (pintype "passive"))
      (node (ref "R131") (pin "2") (pinfunction "2_2") (pintype "passive"))
    )
    (net (code "165") (name "Net-(J17-Pad7)") (class "Default")
      (node (ref "J17") (pin "7") (pinfunction "7_7") (pintype "passive"))
      (node (ref "J29") (pin "1") (pinfunction "1_1") (pintype "passive"))
      (node (ref "R132") (pin "2") (pinfunction "2_2") (pintype "passive"))
    )
    (net (code "166") (name "Net-(J17-Pad8)") (class "Default")
      (node (ref "J17") (pin "8") (pinfunction "8_8") (pintype "passive"))
      (node (ref "J41") (pin "1") (pinfunction "1_1") (pintype "passive"))
      (node (ref "R133") (pin "2") (pinfunction "2_2") (pintype "passive"))
    )
    (net (code "167") (name "Net-(J17-Pad9)") (class "Default")
      (node (ref "J17") (pin "9") (pinfunction "9_9") (pintype "passive"))
      (node (ref "J42") (pin "1") (pinfunction "1_1") (pintype "passive"))
      (node (ref "R134") (pin "2") (pinfunction "2_2") (pintype "passive"))
    )
    (net (code "168") (name "Net-(J17-Pad10)") (class "Default")
      (node (ref "J17") (pin "10") (pinfunction "10_10") (pintype "passive"))
      (node (ref "J45") (pin "1") (pinfunction "1_1") (pintype "passive"))
      (node (ref "R137") (pin "2") (pinfunction "2_2") (pintype "passive"))
    )
    (net (code "169") (name "Net-(J17-Pad11)") (class "Default")
      (node (ref "J17") (pin "11") (pinfunction "11_11") (pintype "passive"))
      (node (ref "J46") (pin "1") (pinfunction "1_1") (pintype "passive"))
      (node (ref "R142") (pin "2") (pinfunction "2_2") (pintype "passive"))
    )
    (net (code "170") (name "Net-(J17-Pad12)") (class "Default")
      (node (ref "J17") (pin "12") (pinfunction "12_12") (pintype "passive"))
      (node (ref "J51") (pin "1") (pinfunction "1_1") (pintype "passive"))
      (node (ref "R145") (pin "2") (pinfunction "2_2") (pintype "passive"))
    )
    (net (code "171") (name "Net-(J17-Pad13)") (class "Default")
      (node (ref "J17") (pin "13") (pinfunction "13_13") (pintype "passive"))
      (node (ref "J56") (pin "1") (pinfunction "1_1") (pintype "passive"))
      (node (ref "R146") (pin "2") (pinfunction "2_2") (pintype "passive"))
    )
    (net (code "172") (name "Net-(J17-Pad14)") (class "Default")
      (node (ref "J17") (pin "14") (pinfunction "14_14") (pintype "passive"))
      (node (ref "J59") (pin "1") (pinfunction "1_1") (pintype "passive"))
      (node (ref "R147") (pin "2") (pinfunction "2_2") (pintype "passive"))
    )
    (net (code "173") (name "Net-(J17-Pad15)") (class "Default")
      (node (ref "J17") (pin "15") (pinfunction "15_15") (pintype "passive"))
      (node (ref "J60") (pin "1") (pinfunction "1_1") (pintype "passive"))
      (node (ref "R150") (pin "2") (pinfunction "2_2") (pintype "passive"))
    )
    (net (code "174") (name "Net-(J18-Pad3)") (class "Default")
      (node (ref "J18") (pin "3") (pinfunction "3_3") (pintype "passive"))
      (node (ref "J23") (pin "1") (pinfunction "1_1") (pintype "passive"))
      (node (ref "R129") (pin "2") (pinfunction "2_2") (pintype "passive"))
    )
    (net (code "175") (name "Net-(J18-Pad4)") (class "Default")
      (node (ref "J18") (pin "4") (pinfunction "4_4") (pintype "passive"))
      (node (ref "J24") (pin "1") (pinfunction "1_1") (pintype "passive"))
      (node (ref "R130") (pin "2") (pinfunction "2_2") (pintype "passive"))
    )
    (net (code "176") (name "Net-(J26-Pad1)") (class "Default")
      (node (ref "J26") (pin "1") (pinfunction "1_1") (pintype "passive"))
      (node (ref "J40") (pin "4") (pinfunction "4_4") (pintype "passive"))
      (node (ref "R136") (pin "2") (pinfunction "2_2") (pintype "passive"))
    )
    (net (code "177") (name "Net-(J27-Pad1)") (class "Default")
      (node (ref "J27") (pin "1") (pinfunction "1_1") (pintype "passive"))
      (node (ref "J40") (pin "3") (pinfunction "3_3") (pintype "passive"))
      (node (ref "R135") (pin "2") (pinfunction "2_2") (pintype "passive"))
    )
    (net (code "178") (name "Net-(J31-Pad1)") (class "Default")
      (node (ref "J31") (pin "1") (pinfunction "1_1") (pintype "passive"))
      (node (ref "J43") (pin "3") (pinfunction "3_3") (pintype "passive"))
      (node (ref "R140") (pin "2") (pinfunction "2_2") (pintype "passive"))
    )
    (net (code "179") (name "Net-(J32-Pad1)") (class "Default")
      (node (ref "J32") (pin "1") (pinfunction "1_1") (pintype "passive"))
      (node (ref "J43") (pin "2") (pinfunction "2_2") (pintype "passive"))
      (node (ref "R139") (pin "2") (pinfunction "2_2") (pintype "passive"))
    )
    (net (code "180") (name "Net-(J36-Pad1)") (class "Default")
      (node (ref "J36") (pin "1") (pinfunction "1_1") (pintype "passive"))
      (node (ref "J44") (pin "5") (pinfunction "5_5") (pintype "passive"))
      (node (ref "R144") (pin "2") (pinfunction "2_2") (pintype "passive"))
    )
    (net (code "181") (name "Net-(J37-Pad1)") (class "Default")
      (node (ref "J37") (pin "1") (pinfunction "1_1") (pintype "passive"))
      (node (ref "J44") (pin "4") (pinfunction "4_4") (pintype "passive"))
      (node (ref "R143") (pin "2") (pinfunction "2_2") (pintype "passive"))
    )
    (net (code "182") (name "Net-(J38-Pad1)") (class "Default")
      (node (ref "J38") (pin "1") (pinfunction "1_1") (pintype "passive"))
      (node (ref "J44") (pin "3") (pinfunction "3_3") (pintype "passive"))
      (node (ref "R141") (pin "2") (pinfunction "2_2") (pintype "passive"))
    )
    (net (code "183") (name "Net-(J39-Pad1)") (class "Default")
      (node (ref "J39") (pin "1") (pinfunction "1_1") (pintype "passive"))
      (node (ref "J44") (pin "2") (pinfunction "2_2") (pintype "passive"))
      (node (ref "R138") (pin "2") (pinfunction "2_2") (pintype "passive"))
    )
    (net (code "184") (name "Net-(J48-Pad1)") (class "Default")
      (node (ref "J48") (pin "1") (pinfunction "1_1") (pintype "passive"))
      (node (ref "J57") (pin "3") (pinfunction "3_3") (pintype "passive"))
      (node (ref "R149") (pin "2") (pinfunction "2_2") (pintype "passive"))
    )
    (net (code "185") (name "Net-(J49-Pad1)") (class "Default")
      (node (ref "J49") (pin "1") (pinfunction "1_1") (pintype "passive"))
      (node (ref "J57") (pin "2") (pinfunction "2_2") (pintype "passive"))
      (node (ref "R148") (pin "2") (pinfunction "2_2") (pintype "passive"))
    )
    (net (code "186") (name "Net-(J53-Pad1)") (class "Default")
      (node (ref "J53") (pin "1") (pinfunction "1_1") (pintype "passive"))
      (node (ref "J58") (pin "3") (pinfunction "3_3") (pintype "passive"))
      (node (ref "R152") (pin "2") (pinfunction "2_2") (pintype "passive"))
    )
    (net (code "187") (name "Net-(J54-Pad1)") (class "Default")
      (node (ref "J54") (pin "1") (pinfunction "1_1") (pintype "passive"))
      (node (ref "J58") (pin "2") (pinfunction "2_2") (pintype "passive"))
      (node (ref "R151") (pin "2") (pinfunction "2_2") (pintype "passive"))
    )
    (net (code "188") (name "Net-(Q11-C1)") (class "Default")
      (node (ref "J10") (pin "1") (pinfunction "1_1") (pintype "passive"))
      (node (ref "Q11") (pin "6") (pinfunction "C1_6") (pintype "passive"))
    )
    (net (code "189") (name "Net-(Q11-C2)") (class "Default")
      (node (ref "J10") (pin "2") (pinfunction "2_2") (pintype "passive"))
      (node (ref "Q11") (pin "3") (pinfunction "C2_3") (pintype "passive"))
    )
    (net (code "190") (name "Net-(Q12-C1)") (class "Default")
      (node (ref "J10") (pin "3") (pinfunction "3_3") (pintype "passive"))
      (node (ref "Q12") (pin "6") (pinfunction "C1_6") (pintype "passive"))
    )
    (net (code "191") (name "Net-(U17-~{HOLD})") (class "Default")
      (node (ref "R155") (pin "2") (pinfunction "2_2") (pintype "passive"))
      (node (ref "U17") (pin "7") (pinfunction "~{HOLD}_7") (pintype "passive"))
    )
    (net (code "192") (name "Net-(U17-~{WP})") (class "Default")
      (node (ref "R153") (pin "2") (pinfunction "2_2") (pintype "passive"))
      (node (ref "U17") (pin "3") (pinfunction "~{WP}_3") (pintype "passive"))
    )
    (net (code "193") (name "Net-(U18-BOOTO)") (class "Default")
      (node (ref "C86") (pin "1") (pinfunction "1_1") (pintype "passive"))
      (node (ref "R158") (pin "2") (pinfunction "2_2") (pintype "passive"))
      (node (ref "U18") (pin "D6") (pinfunction "BOOTO_D6") (pintype "passive"))
    )
    (net (code "194") (name "Net-(U18-PB2{slash}SPI3_MOSI)") (class "Default")
      (node (ref "R162") (pin "2") (pinfunction "2_2") (pintype "passive"))
      (node (ref "U18") (pin "M6") (pinfunction "PB2/SPI3_MOSI_M6") (pintype "passive"))
    )
    (net (code "195") (name "Net-(U18-VCAP_1)") (class "Default")
      (node (ref "C85") (pin "1") (pinfunction "1_1") (pintype "passive"))
      (node (ref "U18") (pin "M10") (pinfunction "VCAP_1_M10") (pintype "passive"))
    )
    (net (code "196") (name "Net-(U18-VCAP_2)") (class "Default")
      (node (ref "C84") (pin "1") (pinfunction "1_1") (pintype "passive"))
      (node (ref "U18") (pin "F13") (pinfunction "VCAP_2_F13") (pintype "passive"))
    )
    (net (code "197") (name "Net-(Y2-O)") (class "Default")
      (node (ref "C92") (pin "1") (pinfunction "1_1") (pintype "passive"))
      (node (ref "R169") (pin "2") (pinfunction "2_2") (pintype "passive"))
      (node (ref "Y2") (pin "3") (pinfunction "O_3") (pintype "passive"))
    )
    (net (code "198") (name "VBAT-1") (class "Default")
      (node (ref "R175") (pin "1") (pinfunction "1_1") (pintype "passive"))
    )
    (net (code "199") (name "unconnected-(J12-USB_ID-Pad4)") (class "Default")
      (node (ref "J12") (pin "4") (pinfunction "USB_ID_4") (pintype "passive"))
    )
    (net (code "200") (name "unconnected-(Q12-B2-Pad5)") (class "Default")
      (node (ref "Q12") (pin "5") (pinfunction "B2_5") (pintype "passive"))
    )
    (net (code "201") (name "unconnected-(Q12-C2-Pad3)") (class "Default")
      (node (ref "Q12") (pin "3") (pinfunction "C2_3") (pintype "passive"))
    )
    (net (code "202") (name "unconnected-(U18-BYPASS___REG-PadL4)") (class "Default")
      (node (ref "U18") (pin "L4") (pinfunction "BYPASS___REG_L4") (pintype "passive"))
    )
  )
)
